# v1-1-0b.net
KiCad netlist of a schematic drawn in EAGLE
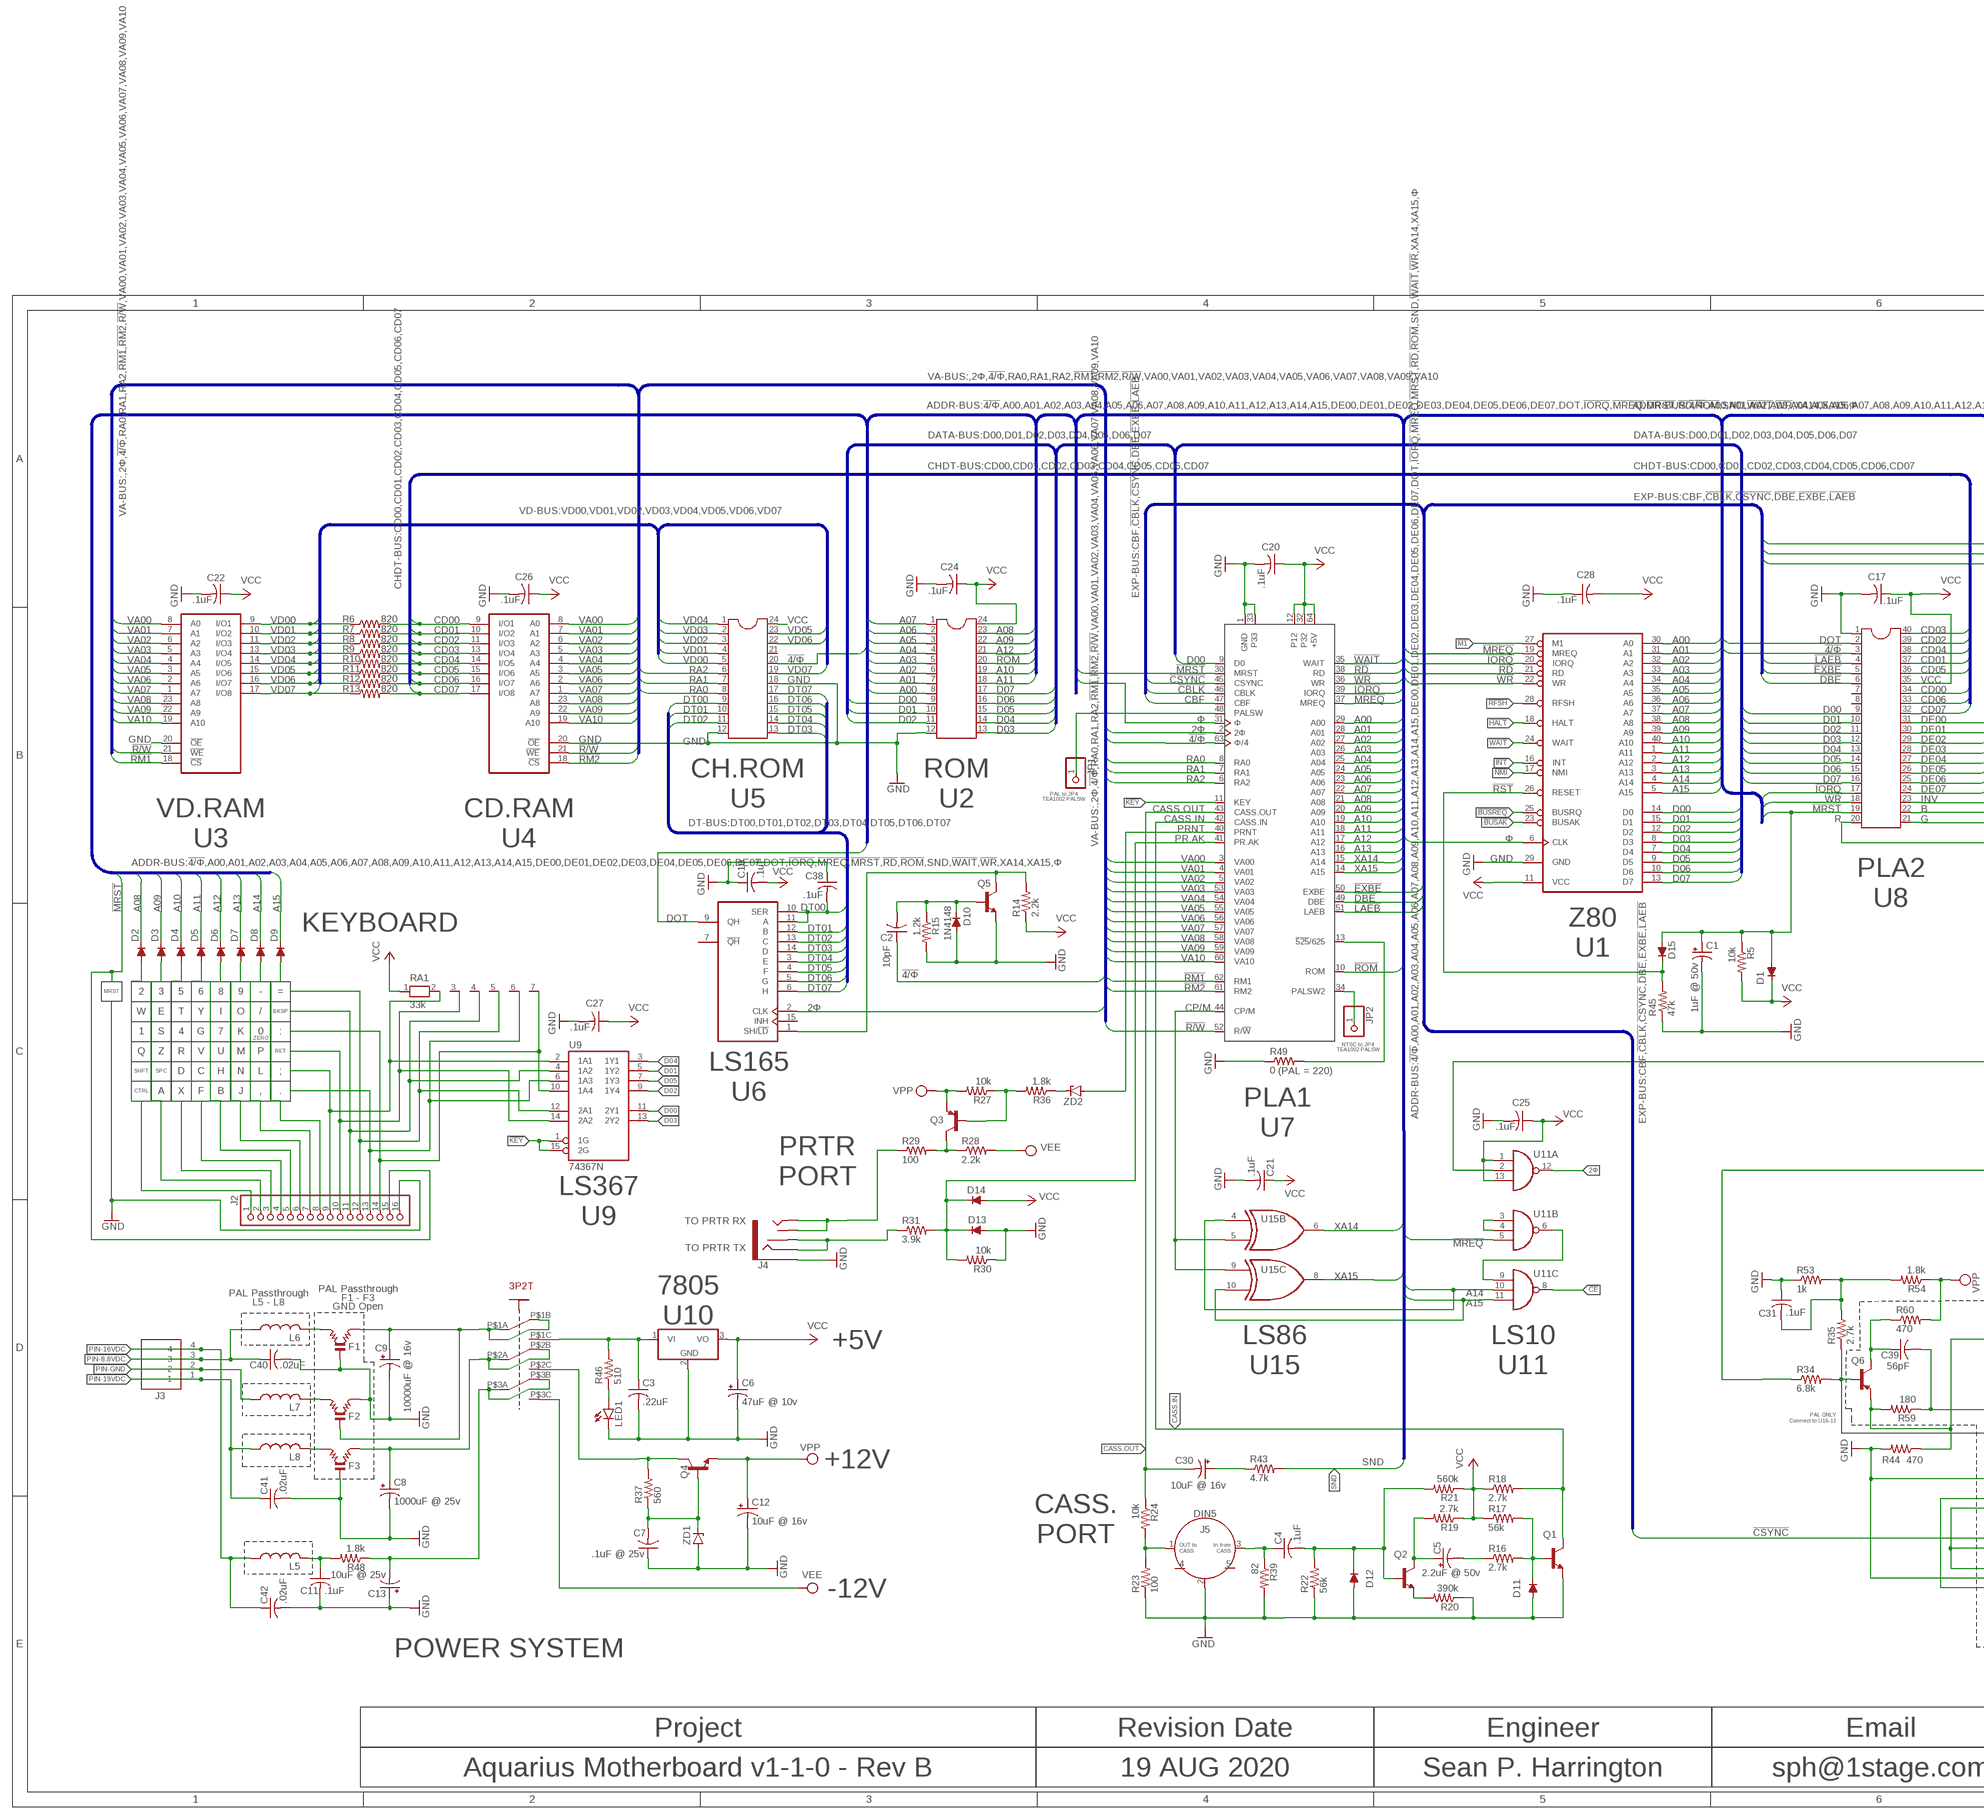
[diagram p0: schematic, sheet 1, part 1 of 2]
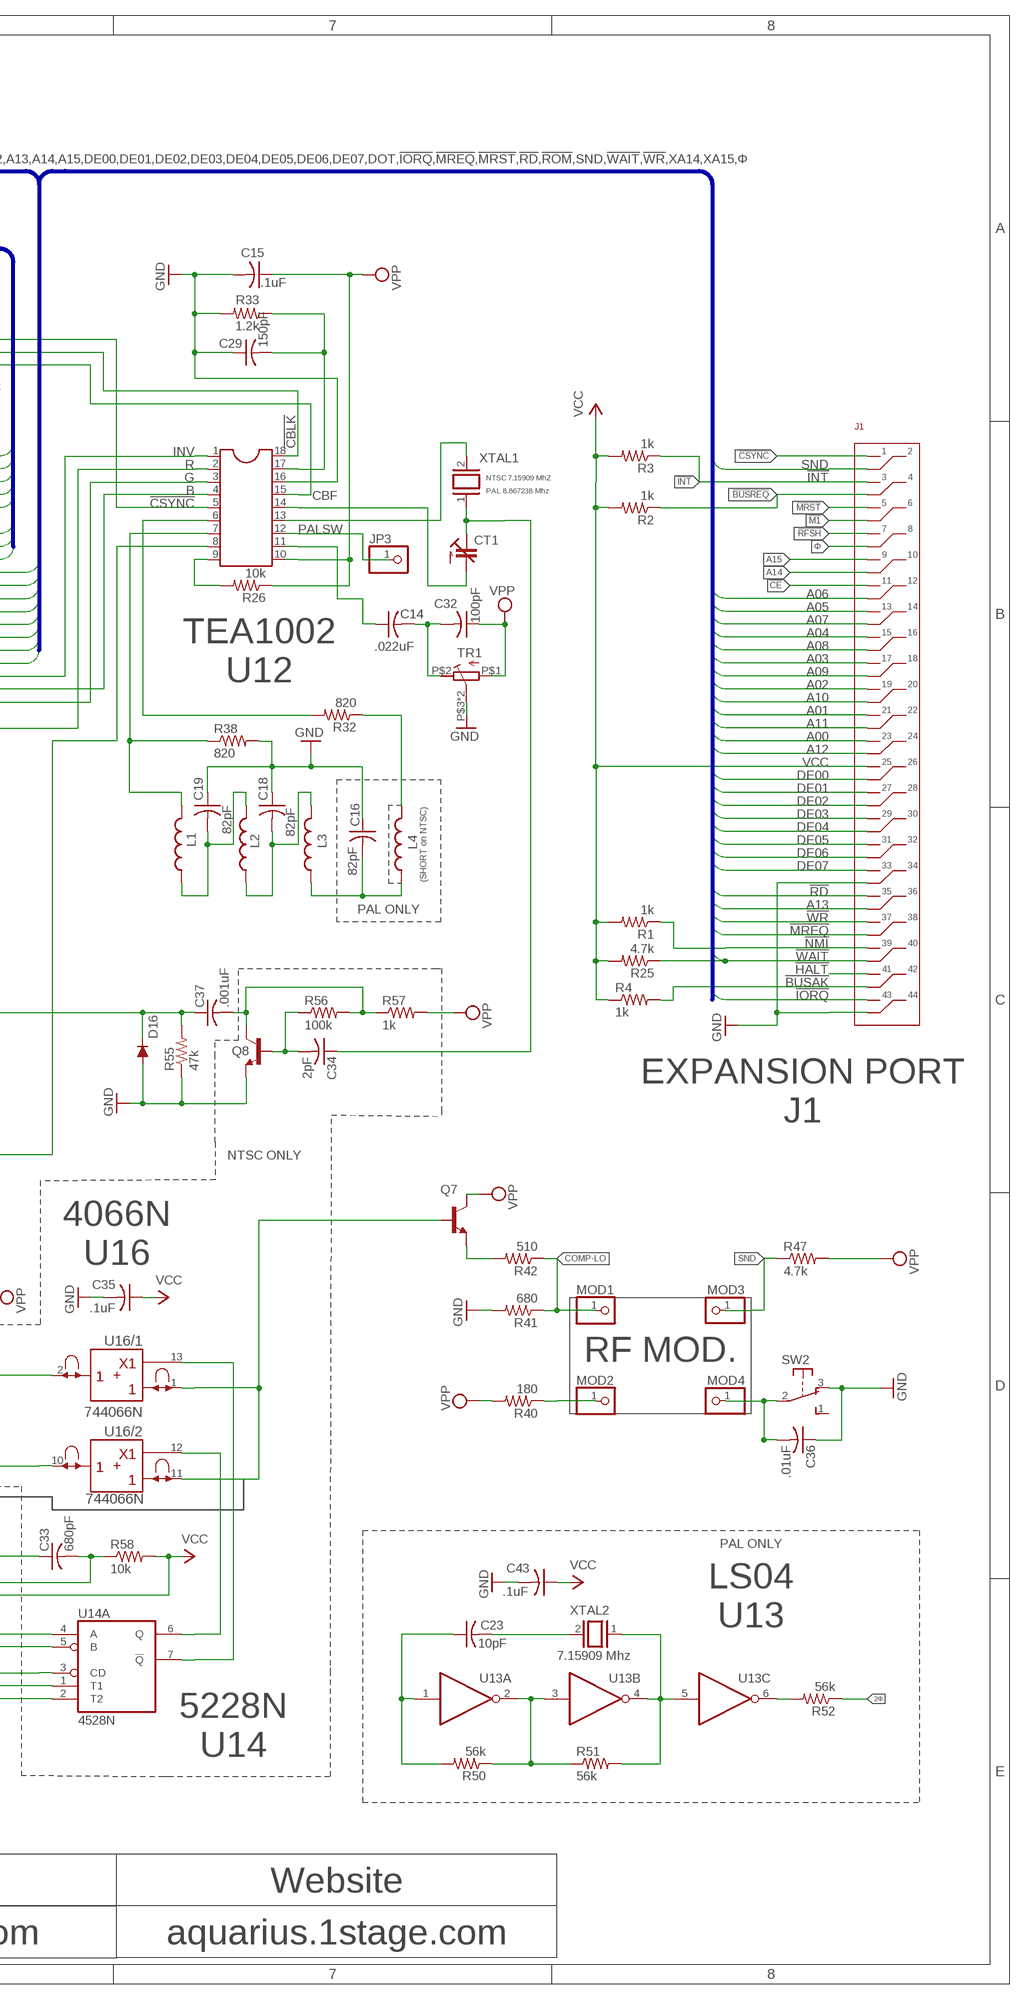
[diagram p1: schematic, sheet 1, part 2 of 2]

(export (version "E")
  (design (tool "Eeschema 10.0.6"))
  (components
    (comp (ref "C1")
      (value "1uF @ 50v")
      (footprint "eagle-import:E2,5-6")
      (libsource (lib "eagle-import") (part "CPOL-USE2.5-6"))
    )
    (comp (ref "C2")
      (value "10pF")
      (footprint "eagle-import:C050-024X044")
      (libsource (lib "eagle-import") (part "C-US050-024X044"))
    )
    (comp (ref "C3")
      (value ".22uF")
      (footprint "eagle-import:C050-025X090")
      (libsource (lib "eagle-import") (part "C-US050-025X090"))
    )
    (comp (ref "C4")
      (value ".1uF")
      (footprint "eagle-import:C050-025X090")
      (libsource (lib "eagle-import") (part "C-US050-025X090"))
    )
    (comp (ref "C5")
      (value "2.2uF @ 50v")
      (footprint "eagle-import:E2,5-6")
      (libsource (lib "eagle-import") (part "CPOL-USE2.5-6"))
    )
    (comp (ref "C6")
      (value "47uF @ 10v")
      (footprint "eagle-import:E2,5-6")
      (libsource (lib "eagle-import") (part "CPOL-USE2.5-6"))
    )
    (comp (ref "C7")
      (value ".1uF @ 25v")
      (footprint "eagle-import:C050-025X090")
      (libsource (lib "eagle-import") (part "C-US050-025X090"))
    )
    (comp (ref "C8")
      (value "1000uF @ 25v")
      (footprint "eagle-import:E7,5-16")
      (libsource (lib "eagle-import") (part "CPOL-USE7.5-16"))
    )
    (comp (ref "C9")
      (value "10000uF @ 16v")
      (footprint "eagle-import:E45-18")
      (libsource (lib "eagle-import") (part "CPOL-USE45-18AXIAL"))
    )
    (comp (ref "C10")
      (value ".1uF")
      (footprint "eagle-import:C050-025X090")
      (libsource (lib "eagle-import") (part "C-US050-025X090"))
    )
    (comp (ref "C11")
      (value ".1uF")
      (footprint "eagle-import:C050-025X090")
      (libsource (lib "eagle-import") (part "C-US050-025X090"))
    )
    (comp (ref "C12")
      (value "10uF @ 16v")
      (footprint "eagle-import:E2,5-6")
      (libsource (lib "eagle-import") (part "CPOL-USE2.5-6"))
    )
    (comp (ref "C13")
      (value "10uF @ 25v")
      (footprint "eagle-import:E2,5-6")
      (libsource (lib "eagle-import") (part "CPOL-USE2.5-6"))
    )
    (comp (ref "C14")
      (value ".022uF")
      (footprint "eagle-import:C050-024X044")
      (libsource (lib "eagle-import") (part "C-US050-024X044"))
    )
    (comp (ref "C15")
      (value ".1uF")
      (footprint "eagle-import:C050-025X090")
      (libsource (lib "eagle-import") (part "C-US050-025X090"))
    )
    (comp (ref "C16")
      (value "82pF")
      (footprint "eagle-import:C050-024X044")
      (libsource (lib "eagle-import") (part "C-US050-024X044"))
    )
    (comp (ref "C17")
      (value ".1uF")
      (footprint "eagle-import:C050-025X090")
      (libsource (lib "eagle-import") (part "C-US050-025X090"))
    )
    (comp (ref "C18")
      (value "82pF")
      (footprint "eagle-import:C050-024X044")
      (libsource (lib "eagle-import") (part "C-US050-024X044"))
    )
    (comp (ref "C19")
      (value "82pF")
      (footprint "eagle-import:C050-024X044")
      (libsource (lib "eagle-import") (part "C-US050-024X044"))
    )
    (comp (ref "C20")
      (value ".1uF")
      (footprint "eagle-import:C050-025X090")
      (libsource (lib "eagle-import") (part "C-US050-025X090"))
    )
    (comp (ref "C21")
      (value ".1uF")
      (footprint "eagle-import:C050-025X090")
      (libsource (lib "eagle-import") (part "C-US050-025X090"))
    )
    (comp (ref "C22")
      (value ".1uF")
      (footprint "eagle-import:C050-025X085")
      (libsource (lib "eagle-import") (part "C-US050-025X085"))
    )
    (comp (ref "C23")
      (value "10pF")
      (footprint "eagle-import:C050-024X044")
      (libsource (lib "eagle-import") (part "C-US050-024X044"))
    )
    (comp (ref "C24")
      (value ".1uF")
      (footprint "eagle-import:C050-025X090")
      (libsource (lib "eagle-import") (part "C-US050-025X090"))
    )
    (comp (ref "C25")
      (value ".1uF")
      (footprint "eagle-import:C050-025X090")
      (libsource (lib "eagle-import") (part "C-US050-025X090"))
    )
    (comp (ref "C26")
      (value ".1uF")
      (footprint "eagle-import:C050-025X085")
      (libsource (lib "eagle-import") (part "C-US050-025X085"))
    )
    (comp (ref "C27")
      (value ".1uF")
      (footprint "eagle-import:C050-025X090")
      (libsource (lib "eagle-import") (part "C-US050-025X090"))
    )
    (comp (ref "C28")
      (value ".1uF")
      (footprint "eagle-import:C050-025X090")
      (libsource (lib "eagle-import") (part "C-US050-025X090"))
    )
    (comp (ref "C29")
      (value "150pF")
      (footprint "eagle-import:C050-024X044")
      (libsource (lib "eagle-import") (part "C-US050-024X044"))
    )
    (comp (ref "C30")
      (value "10uF @ 16v")
      (footprint "eagle-import:E2,5-6")
      (libsource (lib "eagle-import") (part "CPOL-USE2.5-6"))
    )
    (comp (ref "C31")
      (value ".1uF")
      (footprint "eagle-import:C050-024X044")
      (libsource (lib "eagle-import") (part "C-US050-024X044"))
    )
    (comp (ref "C32")
      (value "100pF")
      (footprint "eagle-import:C025-024X044")
      (libsource (lib "eagle-import") (part "C-US025-024X044"))
    )
    (comp (ref "C33")
      (value "680pF")
      (footprint "eagle-import:C050-024X044")
      (libsource (lib "eagle-import") (part "C-US050-024X044"))
    )
    (comp (ref "C34")
      (value "2pF")
      (footprint "eagle-import:C025-024X044")
      (libsource (lib "eagle-import") (part "C-US025-024X044"))
    )
    (comp (ref "C35")
      (value ".1uF")
      (footprint "eagle-import:C050-025X090")
      (libsource (lib "eagle-import") (part "C-US050-025X090"))
    )
    (comp (ref "C36")
      (value ".01uF")
      (footprint "eagle-import:C050-024X044")
      (libsource (lib "eagle-import") (part "C-US050-024X044"))
    )
    (comp (ref "C37")
      (value ".001uF")
      (footprint "eagle-import:C025-030X050")
      (libsource (lib "eagle-import") (part "C-US025-030X050"))
    )
    (comp (ref "C38")
      (value ".1uF")
      (footprint "eagle-import:C050-025X085")
      (libsource (lib "eagle-import") (part "C-US050-025X085"))
    )
    (comp (ref "C39")
      (value "56pF")
      (footprint "eagle-import:C050-024X044")
      (libsource (lib "eagle-import") (part "C-US050-024X044"))
    )
    (comp (ref "C40")
      (value ".02uF")
      (footprint "eagle-import:C050-025X090")
      (libsource (lib "eagle-import") (part "C-US050-025X090"))
    )
    (comp (ref "C41")
      (value ".02uF")
      (footprint "eagle-import:C050-025X090")
      (libsource (lib "eagle-import") (part "C-US050-025X090"))
    )
    (comp (ref "C42")
      (value ".02uF")
      (footprint "eagle-import:C050-025X090")
      (libsource (lib "eagle-import") (part "C-US050-025X090"))
    )
    (comp (ref "C43")
      (value ".1uF")
      (footprint "eagle-import:C050-025X090")
      (libsource (lib "eagle-import") (part "C-US050-025X090"))
    )
    (comp (ref "CT1")
      (value "C-TRIMM808")
      (footprint "eagle-import:CTRIM808-BC")
      (libsource (lib "eagle-import") (part "C-TRIMM808"))
    )
    (comp (ref "D1")
      (value "1N4148")
      (footprint "eagle-import:DO35-10")
      (libsource (lib "eagle-import") (part "1N4148"))
    )
    (comp (ref "D2")
      (value "1N4148H")
      (footprint "eagle-import:DO35-12")
      (libsource (lib "eagle-import") (part "1N4148-12"))
    )
    (comp (ref "D3")
      (value "1N4148H")
      (footprint "eagle-import:DO35-12")
      (libsource (lib "eagle-import") (part "1N4148-12"))
    )
    (comp (ref "D4")
      (value "1N4148H")
      (footprint "eagle-import:DO35-12")
      (libsource (lib "eagle-import") (part "1N4148-12"))
    )
    (comp (ref "D5")
      (value "1N4148H")
      (footprint "eagle-import:DO35-12")
      (libsource (lib "eagle-import") (part "1N4148-12"))
    )
    (comp (ref "D6")
      (value "1N4148H")
      (footprint "eagle-import:DO35-12")
      (libsource (lib "eagle-import") (part "1N4148-12"))
    )
    (comp (ref "D7")
      (value "1N4148H")
      (footprint "eagle-import:DO35-12")
      (libsource (lib "eagle-import") (part "1N4148-12"))
    )
    (comp (ref "D8")
      (value "1N4148H")
      (footprint "eagle-import:DO35-12")
      (libsource (lib "eagle-import") (part "1N4148-12"))
    )
    (comp (ref "D9")
      (value "1N4148H")
      (footprint "eagle-import:DO35-12")
      (libsource (lib "eagle-import") (part "1N4148-12"))
    )
    (comp (ref "D10")
      (value "1N4148")
      (footprint "eagle-import:DO35-10")
      (libsource (lib "eagle-import") (part "1N4148"))
    )
    (comp (ref "D11")
      (value "1N4148")
      (footprint "eagle-import:DO35-10")
      (libsource (lib "eagle-import") (part "1N4148"))
    )
    (comp (ref "D12")
      (value "1N4148")
      (footprint "eagle-import:DO35-10")
      (libsource (lib "eagle-import") (part "1N4148"))
    )
    (comp (ref "D13")
      (value "1N4148")
      (footprint "eagle-import:DO35-10")
      (libsource (lib "eagle-import") (part "1N4148"))
    )
    (comp (ref "D14")
      (value "1N4148")
      (footprint "eagle-import:DO35-10")
      (libsource (lib "eagle-import") (part "1N4148"))
    )
    (comp (ref "D15")
      (value "1N4148")
      (footprint "eagle-import:DO35-10")
      (libsource (lib "eagle-import") (part "1N4148"))
    )
    (comp (ref "D16")
      (value "1N4148")
      (footprint "eagle-import:DO35-10")
      (libsource (lib "eagle-import") (part "1N4148"))
    )
    (comp (ref "F1")
      (value "LCL")
      (footprint "eagle-import:LCL")
      (libsource (lib "eagle-import") (part "LCL"))
    )
    (comp (ref "F2")
      (value "LCL")
      (footprint "eagle-import:LCL")
      (libsource (lib "eagle-import") (part "LCL"))
    )
    (comp (ref "F3")
      (value "LCL")
      (footprint "eagle-import:LCL")
      (libsource (lib "eagle-import") (part "LCL"))
    )
    (comp (ref "J1")
      (value "CR22A-44D-2.54DSA(70)")
      (footprint "eagle-import:CR22A-44D-2.54DSA(70)")
      (libsource (lib "eagle-import") (part "CR22A-44D-2.54DSA(70)"))
    )
    (comp (ref "J2")
      (value "PINHD-1X16")
      (footprint "eagle-import:1X16")
      (libsource (lib "eagle-import") (part "PINHD-1X16"))
    )
    (comp (ref "J3")
      (value "26-60-4040")
      (footprint "eagle-import:SHDR4W155P0X396_1X4_1570X1001X")
      (fields (field (name "MOUSER_PART_NUMBER") "538-26-60-4040"))
      (libsource (lib "eagle-import") (part "26-60-4040"))
    )
    (comp (ref "J4")
      (value "AUDIO_JACK_3.5MM_PTH")
      (footprint "eagle-import:AUDIO-JACK")
      (libsource (lib "eagle-import") (part "AUDIO_JACK_3.5MM_PTH"))
    )
    (comp (ref "J5")
      (value "DIN5")
      (footprint "eagle-import:DIN5-RA-PTH")
      (libsource (lib "eagle-import") (part "DIN5"))
    )
    (comp (ref "JP1")
      (value "PINHD-1X1")
      (footprint "eagle-import:1X01")
      (libsource (lib "eagle-import") (part "PINHD-1X1"))
    )
    (comp (ref "JP2")
      (value "PINHD-1X1")
      (footprint "eagle-import:1X01")
      (libsource (lib "eagle-import") (part "PINHD-1X1"))
    )
    (comp (ref "JP3")
      (value "PINHD-1X1")
      (footprint "eagle-import:1X01")
      (libsource (lib "eagle-import") (part "PINHD-1X1"))
    )
    (comp (ref "L1")
      (value "L-USTFI0305")
      (footprint "eagle-import:TFI0305")
      (libsource (lib "eagle-import") (part "L-USTFI0305"))
    )
    (comp (ref "L2")
      (value "L-USTFI0305")
      (footprint "eagle-import:TFI0305")
      (libsource (lib "eagle-import") (part "L-USTFI0305"))
    )
    (comp (ref "L3")
      (value "L-USTFI0305")
      (footprint "eagle-import:TFI0305")
      (libsource (lib "eagle-import") (part "L-USTFI0305"))
    )
    (comp (ref "L4")
      (value "L-USTFI0305")
      (footprint "eagle-import:TFI0305")
      (libsource (lib "eagle-import") (part "L-USTFI0305"))
    )
    (comp (ref "L5")
      (value "L-USTFI0305")
      (footprint "eagle-import:TFI0305")
      (libsource (lib "eagle-import") (part "L-USTFI0305"))
    )
    (comp (ref "L6")
      (value "L-USTFI0305")
      (footprint "eagle-import:TFI0305")
      (libsource (lib "eagle-import") (part "L-USTFI0305"))
    )
    (comp (ref "L7")
      (value "L-USTFI0305")
      (footprint "eagle-import:TFI0305")
      (libsource (lib "eagle-import") (part "L-USTFI0305"))
    )
    (comp (ref "L8")
      (value "L-USTFI0305")
      (footprint "eagle-import:TFI0305")
      (libsource (lib "eagle-import") (part "L-USTFI0305"))
    )
    (comp (ref "LED1")
      (value "LED5MM")
      (footprint "eagle-import:LED5MM")
      (libsource (lib "eagle-import") (part "LED5MM"))
    )
    (comp (ref "MOD1")
      (value "PINHD-1X1")
      (footprint "eagle-import:1X01")
      (libsource (lib "eagle-import") (part "PINHD-1X1"))
    )
    (comp (ref "MOD2")
      (value "PINHD-1X1")
      (footprint "eagle-import:1X01")
      (libsource (lib "eagle-import") (part "PINHD-1X1"))
    )
    (comp (ref "MOD3")
      (value "PINHD-1X1")
      (footprint "eagle-import:1X01")
      (libsource (lib "eagle-import") (part "PINHD-1X1"))
    )
    (comp (ref "MOD4")
      (value "PINHD-1X1")
      (footprint "eagle-import:1X01")
      (libsource (lib "eagle-import") (part "PINHD-1X1"))
    )
    (comp (ref "Q1")
      (value "-NPN-TO92-E1")
      (footprint "eagle-import:TO92-E1")
      (libsource (lib "eagle-import") (part "-NPN-TO92-E1"))
    )
    (comp (ref "Q2")
      (value "-NPN-TO92-E1")
      (footprint "eagle-import:TO92-E1")
      (libsource (lib "eagle-import") (part "-NPN-TO92-E1"))
    )
    (comp (ref "Q3")
      (value "-PNP-TO92-E1")
      (footprint "eagle-import:TO92-E1")
      (libsource (lib "eagle-import") (part "-PNP-TO92-E1"))
    )
    (comp (ref "Q4")
      (value "-NPN-TO220V")
      (footprint "eagle-import:TO220V")
      (libsource (lib "eagle-import") (part "transistor_402_-NPN-TO220V"))
    )
    (comp (ref "Q5")
      (value "-NPN-TO92-E1")
      (footprint "eagle-import:TO92-E1")
      (libsource (lib "eagle-import") (part "-NPN-TO92-E1"))
    )
    (comp (ref "Q6")
      (value "-PNP-TO92-E1")
      (footprint "eagle-import:TO92-E1")
      (libsource (lib "eagle-import") (part "-PNP-TO92-E1"))
    )
    (comp (ref "Q7")
      (value "-NPN-TO92-E1")
      (footprint "eagle-import:TO92-E1")
      (libsource (lib "eagle-import") (part "-NPN-TO92-E1"))
    )
    (comp (ref "Q8")
      (value "-NPN-TO92-E1")
      (footprint "eagle-import:TO92-E1")
      (libsource (lib "eagle-import") (part "-NPN-TO92-E1"))
    )
    (comp (ref "R1")
      (value "1k")
      (footprint "eagle-import:0207_10")
      (libsource (lib "eagle-import") (part "R-US_0207/10"))
    )
    (comp (ref "R2")
      (value "1k")
      (footprint "eagle-import:0207_10")
      (libsource (lib "eagle-import") (part "R-US_0207/10"))
    )
    (comp (ref "R3")
      (value "1k")
      (footprint "eagle-import:0207_10")
      (libsource (lib "eagle-import") (part "R-US_0207/10"))
    )
    (comp (ref "R4")
      (value "1k")
      (footprint "eagle-import:0207_10")
      (libsource (lib "eagle-import") (part "R-US_0207/10"))
    )
    (comp (ref "R5")
      (value "10k")
      (footprint "eagle-import:0207_10")
      (libsource (lib "eagle-import") (part "R-US_0207/10"))
    )
    (comp (ref "R6")
      (value "820")
      (footprint "eagle-import:0207_10")
      (libsource (lib "eagle-import") (part "R-US_0207/10"))
    )
    (comp (ref "R7")
      (value "820")
      (footprint "eagle-import:0207_10")
      (libsource (lib "eagle-import") (part "R-US_0207/10"))
    )
    (comp (ref "R8")
      (value "820")
      (footprint "eagle-import:0207_10")
      (libsource (lib "eagle-import") (part "R-US_0207/10"))
    )
    (comp (ref "R9")
      (value "820")
      (footprint "eagle-import:0207_10")
      (libsource (lib "eagle-import") (part "R-US_0207/10"))
    )
    (comp (ref "R10")
      (value "820")
      (footprint "eagle-import:0207_10")
      (libsource (lib "eagle-import") (part "R-US_0207/10"))
    )
    (comp (ref "R11")
      (value "820")
      (footprint "eagle-import:0207_10")
      (libsource (lib "eagle-import") (part "R-US_0207/10"))
    )
    (comp (ref "R12")
      (value "820")
      (footprint "eagle-import:0207_10")
      (libsource (lib "eagle-import") (part "R-US_0207/10"))
    )
    (comp (ref "R13")
      (value "820")
      (footprint "eagle-import:0207_10")
      (libsource (lib "eagle-import") (part "R-US_0207/10"))
    )
    (comp (ref "R14")
      (value "2.2k")
      (footprint "eagle-import:0207_10")
      (libsource (lib "eagle-import") (part "R-US_0207/10"))
    )
    (comp (ref "R15")
      (value "1.2k")
      (footprint "eagle-import:0207_10")
      (libsource (lib "eagle-import") (part "R-US_0207/10"))
    )
    (comp (ref "R16")
      (value "2.7k")
      (footprint "eagle-import:0207_10")
      (libsource (lib "eagle-import") (part "R-US_0207/10"))
    )
    (comp (ref "R17")
      (value "56k")
      (footprint "eagle-import:0207_10")
      (libsource (lib "eagle-import") (part "R-US_0207/10"))
    )
    (comp (ref "R18")
      (value "2.7k")
      (footprint "eagle-import:0207_10")
      (libsource (lib "eagle-import") (part "R-US_0207/10"))
    )
    (comp (ref "R19")
      (value "2.7k")
      (footprint "eagle-import:0207_10")
      (libsource (lib "eagle-import") (part "R-US_0207/10"))
    )
    (comp (ref "R20")
      (value "390k")
      (footprint "eagle-import:0207_10")
      (libsource (lib "eagle-import") (part "R-US_0207/10"))
    )
    (comp (ref "R21")
      (value "560k")
      (footprint "eagle-import:0207_10")
      (libsource (lib "eagle-import") (part "R-US_0207/10"))
    )
    (comp (ref "R22")
      (value "56k")
      (footprint "eagle-import:0207_10")
      (libsource (lib "eagle-import") (part "R-US_0207/10"))
    )
    (comp (ref "R23")
      (value "100")
      (footprint "eagle-import:0207_10")
      (libsource (lib "eagle-import") (part "R-US_0207/10"))
    )
    (comp (ref "R24")
      (value "10k")
      (footprint "eagle-import:0207_10")
      (libsource (lib "eagle-import") (part "R-US_0207/10"))
    )
    (comp (ref "R25")
      (value "4.7k")
      (footprint "eagle-import:0207_10")
      (libsource (lib "eagle-import") (part "R-US_0207/10"))
    )
    (comp (ref "R26")
      (value "10k")
      (footprint "eagle-import:0207_10")
      (libsource (lib "eagle-import") (part "R-US_0207/10"))
    )
    (comp (ref "R27")
      (value "10k")
      (footprint "eagle-import:0207_10")
      (libsource (lib "eagle-import") (part "R-US_0207/10"))
    )
    (comp (ref "R28")
      (value "2.2k")
      (footprint "eagle-import:0207_10")
      (libsource (lib "eagle-import") (part "R-US_0207/10"))
    )
    (comp (ref "R29")
      (value "100")
      (footprint "eagle-import:0207_10")
      (libsource (lib "eagle-import") (part "R-US_0207/10"))
    )
    (comp (ref "R30")
      (value "10k")
      (footprint "eagle-import:0207_10")
      (libsource (lib "eagle-import") (part "R-US_0207/10"))
    )
    (comp (ref "R31")
      (value "3.9k")
      (footprint "eagle-import:0207_10")
      (libsource (lib "eagle-import") (part "R-US_0207/10"))
    )
    (comp (ref "R32")
      (value "820")
      (footprint "eagle-import:0207_10")
      (libsource (lib "eagle-import") (part "R-US_0207/10"))
    )
    (comp (ref "R33")
      (value "1.2k")
      (footprint "eagle-import:0207_10")
      (libsource (lib "eagle-import") (part "R-US_0207/10"))
    )
    (comp (ref "R34")
      (value "6.8k")
      (footprint "eagle-import:0207_10")
      (libsource (lib "eagle-import") (part "R-US_0207/10"))
    )
    (comp (ref "R35")
      (value "2.7k")
      (footprint "eagle-import:0207_10")
      (libsource (lib "eagle-import") (part "R-US_0207/10"))
    )
    (comp (ref "R36")
      (value "1.8k")
      (footprint "eagle-import:0207_10")
      (libsource (lib "eagle-import") (part "R-US_0207/10"))
    )
    (comp (ref "R37")
      (value "560")
      (footprint "eagle-import:0207_10")
      (libsource (lib "eagle-import") (part "R-US_0207/10"))
    )
    (comp (ref "R38")
      (value "820")
      (footprint "eagle-import:0207_10")
      (libsource (lib "eagle-import") (part "R-US_0207/10"))
    )
    (comp (ref "R39")
      (value "82")
      (footprint "eagle-import:0207_10")
      (libsource (lib "eagle-import") (part "R-US_0207/10"))
    )
    (comp (ref "R40")
      (value "180")
      (footprint "eagle-import:0207_10")
      (libsource (lib "eagle-import") (part "R-US_0207/10"))
    )
    (comp (ref "R41")
      (value "680")
      (footprint "eagle-import:0207_10")
      (libsource (lib "eagle-import") (part "R-US_0207/10"))
    )
    (comp (ref "R42")
      (value "510")
      (footprint "eagle-import:0207_10")
      (libsource (lib "eagle-import") (part "R-US_0207/10"))
    )
    (comp (ref "R43")
      (value "4.7k")
      (footprint "eagle-import:0207_10")
      (libsource (lib "eagle-import") (part "R-US_0207/10"))
    )
    (comp (ref "R44")
      (value "470")
      (footprint "eagle-import:0207_10")
      (libsource (lib "eagle-import") (part "R-US_0207/10"))
    )
    (comp (ref "R45")
      (value "47k")
      (footprint "eagle-import:0207_10")
      (libsource (lib "eagle-import") (part "R-US_0207/10"))
    )
    (comp (ref "R46")
      (value "510")
      (footprint "eagle-import:0207_10")
      (libsource (lib "eagle-import") (part "R-US_0207/10"))
    )
    (comp (ref "R47")
      (value "4.7k")
      (footprint "eagle-import:0207_10")
      (libsource (lib "eagle-import") (part "R-US_0207/10"))
    )
    (comp (ref "R48")
      (value "1.8k")
      (footprint "eagle-import:0207_10")
      (libsource (lib "eagle-import") (part "R-US_0207/10"))
    )
    (comp (ref "R49")
      (value "0")
      (footprint "eagle-import:0207_7")
      (libsource (lib "eagle-import") (part "R-US_0207/7"))
    )
    (comp (ref "R50")
      (value "56k")
      (footprint "eagle-import:0207_10")
      (libsource (lib "eagle-import") (part "R-US_0207/10"))
    )
    (comp (ref "R51")
      (value "56k")
      (footprint "eagle-import:0207_10")
      (libsource (lib "eagle-import") (part "R-US_0207/10"))
    )
    (comp (ref "R52")
      (value "56k")
      (footprint "eagle-import:0207_10")
      (libsource (lib "eagle-import") (part "R-US_0207/10"))
    )
    (comp (ref "R53")
      (value "1k")
      (footprint "eagle-import:0207_10")
      (libsource (lib "eagle-import") (part "R-US_0207/10"))
    )
    (comp (ref "R54")
      (value "1.8k")
      (footprint "eagle-import:0207_10")
      (libsource (lib "eagle-import") (part "R-US_0207/10"))
    )
    (comp (ref "R55")
      (value "47k")
      (footprint "eagle-import:0207_10")
      (libsource (lib "eagle-import") (part "R-US_0207/10"))
    )
    (comp (ref "R56")
      (value "100k")
      (footprint "eagle-import:0207_10")
      (libsource (lib "eagle-import") (part "R-US_0207/10"))
    )
    (comp (ref "R57")
      (value "1k")
      (footprint "eagle-import:0207_10")
      (libsource (lib "eagle-import") (part "R-US_0207/10"))
    )
    (comp (ref "R58")
      (value "10k")
      (footprint "eagle-import:0207_10")
      (libsource (lib "eagle-import") (part "R-US_0207/10"))
    )
    (comp (ref "R59")
      (value "180")
      (footprint "eagle-import:0207_10")
      (libsource (lib "eagle-import") (part "R-US_0207/10"))
    )
    (comp (ref "R60")
      (value "470")
      (footprint "eagle-import:0207_10")
      (libsource (lib "eagle-import") (part "R-US_0207/10"))
    )
    (comp (ref "RA1")
      (value "33k")
      (footprint "eagle-import:RN-7")
      (libsource (lib "eagle-import") (part "RN06"))
    )
    (comp (ref "SW1")
      (value "3PDT-AQ-SWITCH")
      (footprint "eagle-import:3PDT-AQ-SWITCH")
      (libsource (lib "eagle-import") (part "3PDT-AQ-SWITCH"))
    )
    (comp (ref "SW2")
      (value "9077-1")
      (footprint "eagle-import:9077-1")
      (libsource (lib "eagle-import") (part "9077-1"))
    )
    (comp (ref "TR1")
      (value "R-TRIMM10MM-DUAL")
      (footprint "eagle-import:10MM-DUAL")
      (libsource (lib "eagle-import") (part "R-TRIMM10MM-DUAL"))
    )
    (comp (ref "U1")
      (value "Z80CPU")
      (footprint "eagle-import:DIL40")
      (libsource (lib "eagle-import") (part "Z80CPU"))
    )
    (comp (ref "U2")
      (value "DIL24-6")
      (footprint "eagle-import:DIL24-6")
      (libsource (lib "eagle-import") (part "DIL24-6"))
    )
    (comp (ref "U3")
      (value "6116P")
      (footprint "eagle-import:DIL24-6")
      (libsource (lib "eagle-import") (part "6116P"))
    )
    (comp (ref "U4")
      (value "6116P")
      (footprint "eagle-import:DIL24-6")
      (libsource (lib "eagle-import") (part "6116P"))
    )
    (comp (ref "U5")
      (value "DIL24-6")
      (footprint "eagle-import:DIL24-6")
      (libsource (lib "eagle-import") (part "DIL24-6"))
    )
    (comp (ref "U6")
      (value "74LS165N")
      (footprint "eagle-import:DIL16")
      (libsource (lib "eagle-import") (part "74165NLS"))
    )
    (comp (ref "U7")
      (value "HD61K202P-PLA1")
      (footprint "eagle-import:HD61K202P-PLA1")
      (libsource (lib "eagle-import") (part "HD61K202P-PLA1"))
    )
    (comp (ref "U8")
      (value "DIL40")
      (footprint "eagle-import:DIL40")
      (libsource (lib "eagle-import") (part "DIL40"))
    )
    (comp (ref "U9")
      (value "74367N")
      (footprint "eagle-import:DIL16")
      (libsource (lib "eagle-import") (part "74367N"))
    )
    (comp (ref "U10")
      (value "7805")
      (footprint "eagle-import:TO220V")
      (libsource (lib "eagle-import") (part "78TV05"))
    )
    (comp (ref "U11")
      (value "74LS10N")
      (footprint "eagle-import:DIL14")
      (libsource (lib "eagle-import") (part "7410NLS"))
    )
    (comp (ref "U12")
      (value "DIL18")
      (footprint "eagle-import:DIL18")
      (libsource (lib "eagle-import") (part "DIL18"))
    )
    (comp (ref "U13")
      (value "74LS04N")
      (footprint "eagle-import:DIL14")
      (libsource (lib "eagle-import") (part "7404NLS"))
    )
    (comp (ref "U14")
      (value "4528N")
      (footprint "eagle-import:DIL16")
      (libsource (lib "eagle-import") (part "4528N"))
    )
    (comp (ref "U15")
      (value "74LS86N")
      (footprint "eagle-import:DIL14")
      (libsource (lib "eagle-import") (part "7486NLS"))
    )
    (comp (ref "U16")
      (value "744066N")
      (footprint "eagle-import:DIL14")
      (libsource (lib "eagle-import") (part "744066N"))
    )
    (comp (ref "XTAL1")
      (value "7.15909 MhZ")
      (footprint "eagle-import:Q")
      (libsource (lib "eagle-import") (part "XTAL"))
    )
    (comp (ref "XTAL2")
      (value "7.15909 Mhz")
      (footprint "eagle-import:Q")
      (libsource (lib "eagle-import") (part "XTAL"))
    )
    (comp (ref "ZD1")
      (value "ZENER-DIODEZD-10")
      (footprint "eagle-import:ZDIO-10")
      (libsource (lib "eagle-import") (part "ZENER-DIODEZD-10"))
    )
    (comp (ref "ZD2")
      (value "ZENER-DIODEZD-7.5")
      (footprint "eagle-import:ZDIO-7.5")
      (libsource (lib "eagle-import") (part "ZENER-DIODEZD-7.5"))
    )
  )
  (nets
    (net (code "8") (name "/A00") (class "Default")
      (node (ref "J1") (pin "P$23") (pinfunction "X23_P$23") (pintype "bidirectional"))
      (node (ref "U1") (pin "30") (pinfunction "A0_30") (pintype "output"))
      (node (ref "U2") (pin "8") (pinfunction "8_8") (pintype "passive"))
      (node (ref "U7") (pin "29") (pinfunction "A00_29") (pintype "bidirectional"))
    )
    (net (code "9") (name "/A01") (class "Default")
      (node (ref "J1") (pin "P$21") (pinfunction "X21_P$21") (pintype "bidirectional"))
      (node (ref "U1") (pin "31") (pinfunction "A1_31") (pintype "output"))
      (node (ref "U2") (pin "7") (pinfunction "7_7") (pintype "passive"))
      (node (ref "U7") (pin "28") (pinfunction "A01_28") (pintype "bidirectional"))
    )
    (net (code "10") (name "/A02") (class "Default")
      (node (ref "J1") (pin "P$19") (pinfunction "X19_P$19") (pintype "bidirectional"))
      (node (ref "U1") (pin "32") (pinfunction "A2_32") (pintype "output"))
      (node (ref "U2") (pin "6") (pinfunction "6_6") (pintype "passive"))
      (node (ref "U7") (pin "27") (pinfunction "A02_27") (pintype "bidirectional"))
    )
    (net (code "11") (name "/A03") (class "Default")
      (node (ref "J1") (pin "P$17") (pinfunction "X17_P$17") (pintype "bidirectional"))
      (node (ref "U1") (pin "33") (pinfunction "A3_33") (pintype "output"))
      (node (ref "U2") (pin "5") (pinfunction "5_5") (pintype "passive"))
      (node (ref "U7") (pin "26") (pinfunction "A03_26") (pintype "bidirectional"))
    )
    (net (code "12") (name "/A04") (class "Default")
      (node (ref "J1") (pin "P$15") (pinfunction "X15_P$15") (pintype "bidirectional"))
      (node (ref "U1") (pin "34") (pinfunction "A4_34") (pintype "output"))
      (node (ref "U2") (pin "4") (pinfunction "4_4") (pintype "passive"))
      (node (ref "U7") (pin "25") (pinfunction "A04_25") (pintype "bidirectional"))
    )
    (net (code "13") (name "/A05") (class "Default")
      (node (ref "J1") (pin "P$13") (pinfunction "X13_P$13") (pintype "bidirectional"))
      (node (ref "U1") (pin "35") (pinfunction "A5_35") (pintype "output"))
      (node (ref "U2") (pin "3") (pinfunction "3_3") (pintype "passive"))
      (node (ref "U7") (pin "24") (pinfunction "A05_24") (pintype "bidirectional"))
    )
    (net (code "14") (name "/A06") (class "Default")
      (node (ref "J1") (pin "P$12") (pinfunction "X12_P$12") (pintype "bidirectional"))
      (node (ref "U1") (pin "36") (pinfunction "A6_36") (pintype "output"))
      (node (ref "U2") (pin "2") (pinfunction "2_2") (pintype "passive"))
      (node (ref "U7") (pin "23") (pinfunction "A06_23") (pintype "bidirectional"))
    )
    (net (code "15") (name "/A07") (class "Default")
      (node (ref "J1") (pin "P$14") (pinfunction "X14_P$14") (pintype "bidirectional"))
      (node (ref "U1") (pin "37") (pinfunction "A7_37") (pintype "output"))
      (node (ref "U2") (pin "1") (pinfunction "1_1") (pintype "passive"))
      (node (ref "U7") (pin "22") (pinfunction "A07_22") (pintype "bidirectional"))
    )
    (net (code "16") (name "/A08") (class "Default")
      (node (ref "D2") (pin "C") (pinfunction "C_C") (pintype "passive"))
      (node (ref "J1") (pin "P$16") (pinfunction "X16_P$16") (pintype "bidirectional"))
      (node (ref "U1") (pin "38") (pinfunction "A8_38") (pintype "output"))
      (node (ref "U2") (pin "23") (pinfunction "23_23") (pintype "passive"))
      (node (ref "U7") (pin "21") (pinfunction "A08_21") (pintype "bidirectional"))
    )
    (net (code "17") (name "/A09") (class "Default")
      (node (ref "D3") (pin "C") (pinfunction "C_C") (pintype "passive"))
      (node (ref "J1") (pin "P$18") (pinfunction "X18_P$18") (pintype "bidirectional"))
      (node (ref "U1") (pin "39") (pinfunction "A9_39") (pintype "output"))
      (node (ref "U2") (pin "22") (pinfunction "22_22") (pintype "passive"))
      (node (ref "U7") (pin "20") (pinfunction "A09_20") (pintype "bidirectional"))
    )
    (net (code "18") (name "/A10") (class "Default")
      (node (ref "D4") (pin "C") (pinfunction "C_C") (pintype "passive"))
      (node (ref "J1") (pin "P$20") (pinfunction "X20_P$20") (pintype "bidirectional"))
      (node (ref "U1") (pin "40") (pinfunction "A10_40") (pintype "output"))
      (node (ref "U2") (pin "19") (pinfunction "19_19") (pintype "passive"))
      (node (ref "U7") (pin "19") (pinfunction "A10_19") (pintype "bidirectional"))
    )
    (net (code "19") (name "/A11") (class "Default")
      (node (ref "D5") (pin "C") (pinfunction "C_C") (pintype "passive"))
      (node (ref "J1") (pin "P$22") (pinfunction "X22_P$22") (pintype "bidirectional"))
      (node (ref "U1") (pin "1") (pinfunction "A11_1") (pintype "output"))
      (node (ref "U2") (pin "18") (pinfunction "18_18") (pintype "passive"))
      (node (ref "U7") (pin "18") (pinfunction "A11_18") (pintype "bidirectional"))
    )
    (net (code "20") (name "/A12") (class "Default")
      (node (ref "D6") (pin "C") (pinfunction "C_C") (pintype "passive"))
      (node (ref "J1") (pin "P$24") (pinfunction "X24_P$24") (pintype "bidirectional"))
      (node (ref "U1") (pin "2") (pinfunction "A12_2") (pintype "output"))
      (node (ref "U2") (pin "21") (pinfunction "21_21") (pintype "passive"))
      (node (ref "U7") (pin "17") (pinfunction "A12_17") (pintype "bidirectional"))
    )
    (net (code "21") (name "/A13") (class "Default")
      (node (ref "D7") (pin "C") (pinfunction "C_C") (pintype "passive"))
      (node (ref "J1") (pin "P$36") (pinfunction "X36_P$36") (pintype "bidirectional"))
      (node (ref "U1") (pin "3") (pinfunction "A13_3") (pintype "output"))
      (node (ref "U7") (pin "16") (pinfunction "A13_16") (pintype "bidirectional"))
    )
    (net (code "22") (name "/B") (class "Default")
      (node (ref "U12") (pin "4") (pinfunction "4_4") (pintype "passive"))
      (node (ref "U8") (pin "22") (pinfunction "22_22") (pintype "passive"))
    )
    (net (code "23") (name "/CBF") (class "Default")
      (node (ref "U12") (pin "15") (pinfunction "15_15") (pintype "passive"))
      (node (ref "U7") (pin "47") (pinfunction "CBF_47") (pintype "bidirectional"))
    )
    (net (code "24") (name "/CD00") (class "Default")
      (node (ref "R6") (pin "2") (pinfunction "2_2") (pintype "passive"))
      (node (ref "U4") (pin "9") (pinfunction "I/O1_9") (pintype "bidirectional"))
      (node (ref "U8") (pin "34") (pinfunction "34_34") (pintype "passive"))
    )
    (net (code "25") (name "/CD01") (class "Default")
      (node (ref "R7") (pin "2") (pinfunction "2_2") (pintype "passive"))
      (node (ref "U4") (pin "10") (pinfunction "I/O2_10") (pintype "bidirectional"))
      (node (ref "U8") (pin "37") (pinfunction "37_37") (pintype "passive"))
    )
    (net (code "26") (name "/CD02") (class "Default")
      (node (ref "R8") (pin "2") (pinfunction "2_2") (pintype "passive"))
      (node (ref "U4") (pin "11") (pinfunction "I/O3_11") (pintype "bidirectional"))
      (node (ref "U8") (pin "39") (pinfunction "39_39") (pintype "passive"))
    )
    (net (code "27") (name "/CD03") (class "Default")
      (node (ref "R9") (pin "2") (pinfunction "2_2") (pintype "passive"))
      (node (ref "U4") (pin "13") (pinfunction "I/O4_13") (pintype "bidirectional"))
      (node (ref "U8") (pin "40") (pinfunction "40_40") (pintype "passive"))
    )
    (net (code "28") (name "/CD04") (class "Default")
      (node (ref "R10") (pin "2") (pinfunction "2_2") (pintype "passive"))
      (node (ref "U4") (pin "14") (pinfunction "I/O5_14") (pintype "bidirectional"))
      (node (ref "U8") (pin "38") (pinfunction "38_38") (pintype "passive"))
    )
    (net (code "29") (name "/CD05") (class "Default")
      (node (ref "R11") (pin "2") (pinfunction "2_2") (pintype "passive"))
      (node (ref "U4") (pin "15") (pinfunction "I/O6_15") (pintype "bidirectional"))
      (node (ref "U8") (pin "36") (pinfunction "36_36") (pintype "passive"))
    )
    (net (code "30") (name "/CD06") (class "Default")
      (node (ref "R12") (pin "2") (pinfunction "2_2") (pintype "passive"))
      (node (ref "U4") (pin "16") (pinfunction "I/O7_16") (pintype "bidirectional"))
      (node (ref "U8") (pin "33") (pinfunction "33_33") (pintype "passive"))
    )
    (net (code "31") (name "/CD07") (class "Default")
      (node (ref "R13") (pin "2") (pinfunction "2_2") (pintype "passive"))
      (node (ref "U4") (pin "17") (pinfunction "I/O8_17") (pintype "bidirectional"))
      (node (ref "U8") (pin "32") (pinfunction "32_32") (pintype "passive"))
    )
    (net (code "32") (name "/CP{slash}M") (class "Default")
      (node (ref "U15") (pin "5") (pinfunction "I1_5") (pintype "input"))
      (node (ref "U15") (pin "9") (pinfunction "I0_9") (pintype "input"))
      (node (ref "U7") (pin "44") (pinfunction "CP/M_44") (pintype "bidirectional"))
    )
    (net (code "33") (name "/D06") (class "Default")
      (node (ref "U1") (pin "10") (pinfunction "D6_10") (pintype "bidirectional"))
      (node (ref "U2") (pin "16") (pinfunction "16_16") (pintype "passive"))
      (node (ref "U8") (pin "15") (pinfunction "15_15") (pintype "passive"))
    )
    (net (code "34") (name "/D07") (class "Default")
      (node (ref "U1") (pin "13") (pinfunction "D7_13") (pintype "bidirectional"))
      (node (ref "U2") (pin "17") (pinfunction "17_17") (pintype "passive"))
      (node (ref "U8") (pin "16") (pinfunction "16_16") (pintype "passive"))
    )
    (net (code "35") (name "/DE00") (class "Default")
      (node (ref "J1") (pin "P$26") (pinfunction "X26_P$26") (pintype "bidirectional"))
      (node (ref "U8") (pin "31") (pinfunction "31_31") (pintype "passive"))
    )
    (net (code "36") (name "/DE01") (class "Default")
      (node (ref "J1") (pin "P$27") (pinfunction "X27_P$27") (pintype "bidirectional"))
      (node (ref "U8") (pin "30") (pinfunction "30_30") (pintype "passive"))
    )
    (net (code "37") (name "/DE02") (class "Default")
      (node (ref "J1") (pin "P$28") (pinfunction "X28_P$28") (pintype "bidirectional"))
      (node (ref "U8") (pin "29") (pinfunction "29_29") (pintype "passive"))
    )
    (net (code "38") (name "/DE03") (class "Default")
      (node (ref "J1") (pin "P$29") (pinfunction "X29_P$29") (pintype "bidirectional"))
      (node (ref "U8") (pin "28") (pinfunction "28_28") (pintype "passive"))
    )
    (net (code "39") (name "/DE04") (class "Default")
      (node (ref "J1") (pin "P$30") (pinfunction "X30_P$30") (pintype "bidirectional"))
      (node (ref "U8") (pin "27") (pinfunction "27_27") (pintype "passive"))
    )
    (net (code "40") (name "/DE05") (class "Default")
      (node (ref "J1") (pin "P$31") (pinfunction "X31_P$31") (pintype "bidirectional"))
      (node (ref "U8") (pin "26") (pinfunction "26_26") (pintype "passive"))
    )
    (net (code "41") (name "/DE06") (class "Default")
      (node (ref "J1") (pin "P$32") (pinfunction "X32_P$32") (pintype "bidirectional"))
      (node (ref "U8") (pin "25") (pinfunction "25_25") (pintype "passive"))
    )
    (net (code "42") (name "/DE07") (class "Default")
      (node (ref "J1") (pin "P$33") (pinfunction "X33_P$33") (pintype "bidirectional"))
      (node (ref "U8") (pin "24") (pinfunction "24_24") (pintype "passive"))
    )
    (net (code "43") (name "/DOT") (class "Default")
      (node (ref "U6") (pin "9") (pinfunction "QH_9") (pintype "output"))
      (node (ref "U8") (pin "2") (pinfunction "2_2") (pintype "passive"))
    )
    (net (code "44") (name "/DT00") (class "Default")
      (node (ref "C38") (pin "2") (pinfunction "2_2") (pintype "passive"))
      (node (ref "U5") (pin "9") (pinfunction "9_9") (pintype "passive"))
      (node (ref "U6") (pin "10") (pinfunction "SER_10") (pintype "input"))
      (node (ref "U6") (pin "11") (pinfunction "A_11") (pintype "input"))
    )
    (net (code "45") (name "/DT01") (class "Default")
      (node (ref "U5") (pin "10") (pinfunction "10_10") (pintype "passive"))
      (node (ref "U6") (pin "12") (pinfunction "B_12") (pintype "input"))
    )
    (net (code "46") (name "/DT02") (class "Default")
      (node (ref "U5") (pin "11") (pinfunction "11_11") (pintype "passive"))
      (node (ref "U6") (pin "13") (pinfunction "C_13") (pintype "input"))
    )
    (net (code "47") (name "/DT03") (class "Default")
      (node (ref "U5") (pin "13") (pinfunction "13_13") (pintype "passive"))
      (node (ref "U6") (pin "14") (pinfunction "D_14") (pintype "input"))
    )
    (net (code "48") (name "/DT04") (class "Default")
      (node (ref "U5") (pin "14") (pinfunction "14_14") (pintype "passive"))
      (node (ref "U6") (pin "3") (pinfunction "E_3") (pintype "input"))
    )
    (net (code "49") (name "/DT05") (class "Default")
      (node (ref "U5") (pin "15") (pinfunction "15_15") (pintype "passive"))
      (node (ref "U6") (pin "4") (pinfunction "F_4") (pintype "input"))
    )
    (net (code "50") (name "/DT06") (class "Default")
      (node (ref "U5") (pin "16") (pinfunction "16_16") (pintype "passive"))
      (node (ref "U6") (pin "5") (pinfunction "G_5") (pintype "input"))
    )
    (net (code "51") (name "/DT07") (class "Default")
      (node (ref "U5") (pin "17") (pinfunction "17_17") (pintype "passive"))
      (node (ref "U6") (pin "6") (pinfunction "H_6") (pintype "input"))
    )
    (net (code "52") (name "/G") (class "Default")
      (node (ref "U12") (pin "3") (pinfunction "3_3") (pintype "passive"))
      (node (ref "U8") (pin "21") (pinfunction "21_21") (pintype "passive"))
    )
    (net (code "53") (name "/INV") (class "Default")
      (node (ref "U12") (pin "1") (pinfunction "1_1") (pintype "passive"))
      (node (ref "U8") (pin "23") (pinfunction "23_23") (pintype "passive"))
    )
    (net (code "54") (name "/PALSW") (class "Default")
      (node (ref "JP3") (pin "1") (pinfunction "1_1") (pintype "passive"))
      (node (ref "U12") (pin "12") (pinfunction "12_12") (pintype "passive"))
    )
    (net (code "55") (name "/PR.AK") (class "Default")
      (node (ref "D13") (pin "C") (pinfunction "C_C") (pintype "passive"))
      (node (ref "D14") (pin "C") (pinfunction "C_C") (pintype "passive"))
      (node (ref "R30") (pin "2") (pinfunction "2_2") (pintype "passive"))
      (node (ref "R31") (pin "2") (pinfunction "2_2") (pintype "passive"))
      (node (ref "U7") (pin "41") (pinfunction "PR.AK_41") (pintype "bidirectional"))
    )
    (net (code "56") (name "/PRNT") (class "Default")
      (node (ref "U7") (pin "40") (pinfunction "PRNT_40") (pintype "bidirectional"))
      (node (ref "ZD2") (pin "A") (pinfunction "A_A") (pintype "passive"))
    )
    (net (code "57") (name "/R") (class "Default")
      (node (ref "U12") (pin "2") (pinfunction "2_2") (pintype "passive"))
      (node (ref "U8") (pin "20") (pinfunction "20_20") (pintype "passive"))
    )
    (net (code "58") (name "/RA0") (class "Default")
      (node (ref "U5") (pin "8") (pinfunction "8_8") (pintype "passive"))
      (node (ref "U7") (pin "8") (pinfunction "RA0_8") (pintype "bidirectional"))
    )
    (net (code "59") (name "/RA1") (class "Default")
      (node (ref "U5") (pin "7") (pinfunction "7_7") (pintype "passive"))
      (node (ref "U7") (pin "7") (pinfunction "RA1_7") (pintype "bidirectional"))
    )
    (net (code "60") (name "/RA2") (class "Default")
      (node (ref "U5") (pin "6") (pinfunction "6_6") (pintype "passive"))
      (node (ref "U7") (pin "6") (pinfunction "RA2_6") (pintype "bidirectional"))
    )
    (net (code "61") (name "/VA00") (class "Default")
      (node (ref "U3") (pin "8") (pinfunction "A0_8") (pintype "input"))
      (node (ref "U4") (pin "8") (pinfunction "A0_8") (pintype "input"))
      (node (ref "U7") (pin "3") (pinfunction "VA00_3") (pintype "bidirectional"))
    )
    (net (code "62") (name "/VA01") (class "Default")
      (node (ref "U3") (pin "7") (pinfunction "A1_7") (pintype "input"))
      (node (ref "U4") (pin "7") (pinfunction "A1_7") (pintype "input"))
      (node (ref "U7") (pin "4") (pinfunction "VA01_4") (pintype "bidirectional"))
    )
    (net (code "63") (name "/VA02") (class "Default")
      (node (ref "U3") (pin "6") (pinfunction "A2_6") (pintype "input"))
      (node (ref "U4") (pin "6") (pinfunction "A2_6") (pintype "input"))
      (node (ref "U7") (pin "5") (pinfunction "VA02_5") (pintype "bidirectional"))
    )
    (net (code "64") (name "/VA03") (class "Default")
      (node (ref "U3") (pin "5") (pinfunction "A3_5") (pintype "input"))
      (node (ref "U4") (pin "5") (pinfunction "A3_5") (pintype "input"))
      (node (ref "U7") (pin "53") (pinfunction "VA03_53") (pintype "bidirectional"))
    )
    (net (code "65") (name "/VA04") (class "Default")
      (node (ref "U3") (pin "4") (pinfunction "A4_4") (pintype "input"))
      (node (ref "U4") (pin "4") (pinfunction "A4_4") (pintype "input"))
      (node (ref "U7") (pin "54") (pinfunction "VA04_54") (pintype "bidirectional"))
    )
    (net (code "66") (name "/VA05") (class "Default")
      (node (ref "U3") (pin "3") (pinfunction "A5_3") (pintype "input"))
      (node (ref "U4") (pin "3") (pinfunction "A5_3") (pintype "input"))
      (node (ref "U7") (pin "55") (pinfunction "VA05_55") (pintype "bidirectional"))
    )
    (net (code "67") (name "/VA06") (class "Default")
      (node (ref "U3") (pin "2") (pinfunction "A6_2") (pintype "input"))
      (node (ref "U4") (pin "2") (pinfunction "A6_2") (pintype "input"))
      (node (ref "U7") (pin "56") (pinfunction "VA06_56") (pintype "bidirectional"))
    )
    (net (code "68") (name "/VA07") (class "Default")
      (node (ref "U3") (pin "1") (pinfunction "A7_1") (pintype "input"))
      (node (ref "U4") (pin "1") (pinfunction "A7_1") (pintype "input"))
      (node (ref "U7") (pin "57") (pinfunction "VA07_57") (pintype "bidirectional"))
    )
    (net (code "69") (name "/VA08") (class "Default")
      (node (ref "U3") (pin "23") (pinfunction "A8_23") (pintype "input"))
      (node (ref "U4") (pin "23") (pinfunction "A8_23") (pintype "input"))
      (node (ref "U7") (pin "58") (pinfunction "VA08_58") (pintype "bidirectional"))
    )
    (net (code "70") (name "/VA09") (class "Default")
      (node (ref "U3") (pin "22") (pinfunction "A9_22") (pintype "input"))
      (node (ref "U4") (pin "22") (pinfunction "A9_22") (pintype "input"))
      (node (ref "U7") (pin "59") (pinfunction "VA09_59") (pintype "bidirectional"))
    )
    (net (code "71") (name "/VA10") (class "Default")
      (node (ref "U3") (pin "19") (pinfunction "A10_19") (pintype "input"))
      (node (ref "U4") (pin "19") (pinfunction "A10_19") (pintype "input"))
      (node (ref "U7") (pin "60") (pinfunction "VA10_60") (pintype "bidirectional"))
    )
    (net (code "72") (name "/VD00") (class "Default")
      (node (ref "R6") (pin "1") (pinfunction "1_1") (pintype "passive"))
      (node (ref "U3") (pin "9") (pinfunction "I/O1_9") (pintype "bidirectional"))
      (node (ref "U5") (pin "5") (pinfunction "5_5") (pintype "passive"))
    )
    (net (code "73") (name "/VD01") (class "Default")
      (node (ref "R7") (pin "1") (pinfunction "1_1") (pintype "passive"))
      (node (ref "U3") (pin "10") (pinfunction "I/O2_10") (pintype "bidirectional"))
      (node (ref "U5") (pin "4") (pinfunction "4_4") (pintype "passive"))
    )
    (net (code "74") (name "/VD02") (class "Default")
      (node (ref "R8") (pin "1") (pinfunction "1_1") (pintype "passive"))
      (node (ref "U3") (pin "11") (pinfunction "I/O3_11") (pintype "bidirectional"))
      (node (ref "U5") (pin "3") (pinfunction "3_3") (pintype "passive"))
    )
    (net (code "75") (name "/VD03") (class "Default")
      (node (ref "R9") (pin "1") (pinfunction "1_1") (pintype "passive"))
      (node (ref "U3") (pin "13") (pinfunction "I/O4_13") (pintype "bidirectional"))
      (node (ref "U5") (pin "2") (pinfunction "2_2") (pintype "passive"))
    )
    (net (code "76") (name "/VD04") (class "Default")
      (node (ref "R10") (pin "1") (pinfunction "1_1") (pintype "passive"))
      (node (ref "U3") (pin "14") (pinfunction "I/O5_14") (pintype "bidirectional"))
      (node (ref "U5") (pin "1") (pinfunction "1_1") (pintype "passive"))
    )
    (net (code "77") (name "/VD05") (class "Default")
      (node (ref "R11") (pin "1") (pinfunction "1_1") (pintype "passive"))
      (node (ref "U3") (pin "15") (pinfunction "I/O6_15") (pintype "bidirectional"))
      (node (ref "U5") (pin "23") (pinfunction "23_23") (pintype "passive"))
    )
    (net (code "78") (name "/VD06") (class "Default")
      (node (ref "R12") (pin "1") (pinfunction "1_1") (pintype "passive"))
      (node (ref "U3") (pin "16") (pinfunction "I/O7_16") (pintype "bidirectional"))
      (node (ref "U5") (pin "22") (pinfunction "22_22") (pintype "passive"))
    )
    (net (code "79") (name "/VD07") (class "Default")
      (node (ref "R13") (pin "1") (pinfunction "1_1") (pintype "passive"))
      (node (ref "U3") (pin "17") (pinfunction "I/O8_17") (pintype "bidirectional"))
      (node (ref "U5") (pin "19") (pinfunction "19_19") (pintype "passive"))
    )
    (net (code "80") (name "/XA14") (class "Default")
      (node (ref "U15") (pin "6") (pinfunction "O_6") (pintype "output"))
      (node (ref "U7") (pin "15") (pinfunction "A14_15") (pintype "bidirectional"))
    )
    (net (code "81") (name "/XA15") (class "Default")
      (node (ref "U15") (pin "8") (pinfunction "O_8") (pintype "output"))
      (node (ref "U7") (pin "14") (pinfunction "A15_14") (pintype "bidirectional"))
    )
    (net (code "89") (name "/~{4{slash}Φ}") (class "Default")
      (node (ref "C2") (pin "1") (pinfunction "1_1") (pintype "passive"))
      (node (ref "U5") (pin "20") (pinfunction "20_20") (pintype "passive"))
      (node (ref "U7") (pin "63") (pinfunction "Φ/4_63") (pintype "bidirectional"))
      (node (ref "U8") (pin "3") (pinfunction "3_3") (pintype "passive"))
    )
    (net (code "90") (name "/~{BUSAK}") (class "Default")
      (node (ref "J1") (pin "P$42") (pinfunction "X42_P$42") (pintype "bidirectional"))
      (node (ref "R4") (pin "2") (pinfunction "2_2") (pintype "passive"))
      (node (ref "U1") (pin "23") (pinfunction "BUSAK_23") (pintype "output"))
    )
    (net (code "91") (name "/~{BUSREQ}") (class "Default")
      (node (ref "J1") (pin "P$4") (pinfunction "X4_P$4") (pintype "bidirectional"))
      (node (ref "R2") (pin "1") (pinfunction "1_1") (pintype "passive"))
      (node (ref "U1") (pin "25") (pinfunction "BUSRQ_25") (pintype "input"))
    )
    (net (code "92") (name "/~{CBLK}") (class "Default")
      (node (ref "U12") (pin "18") (pinfunction "18_18") (pintype "passive"))
      (node (ref "U7") (pin "46") (pinfunction "CBLK_46") (pintype "bidirectional"))
    )
    (net (code "93") (name "/~{CE}") (class "Default")
      (node (ref "J1") (pin "P$11") (pinfunction "X11_P$11") (pintype "bidirectional"))
      (node (ref "U11") (pin "8") (pinfunction "O_8") (pintype "output"))
    )
    (net (code "94") (name "/~{CSYNC}") (class "Default")
      (node (ref "J1") (pin "P$1") (pinfunction "X1_P$1") (pintype "bidirectional"))
      (node (ref "U12") (pin "5") (pinfunction "5_5") (pintype "passive"))
      (node (ref "U14") (pin "4") (pinfunction "A_4") (pintype "input"))
      (node (ref "U7") (pin "45") (pinfunction "CSYNC_45") (pintype "bidirectional"))
    )
    (net (code "95") (name "/~{DBE}") (class "Default")
      (node (ref "U7") (pin "49") (pinfunction "DBE_49") (pintype "bidirectional"))
      (node (ref "U8") (pin "6") (pinfunction "6_6") (pintype "passive"))
    )
    (net (code "96") (name "/~{EXBE}") (class "Default")
      (node (ref "U7") (pin "50") (pinfunction "EXBE_50") (pintype "bidirectional"))
      (node (ref "U8") (pin "5") (pinfunction "5_5") (pintype "passive"))
    )
    (net (code "97") (name "/~{HALT}") (class "Default")
      (node (ref "J1") (pin "P$41") (pinfunction "X41_P$41") (pintype "bidirectional"))
      (node (ref "U1") (pin "18") (pinfunction "HALT_18") (pintype "output"))
    )
    (net (code "98") (name "/~{INT}") (class "Default")
      (node (ref "J1") (pin "P$3") (pinfunction "X3_P$3") (pintype "bidirectional"))
      (node (ref "R3") (pin "1") (pinfunction "1_1") (pintype "passive"))
      (node (ref "U1") (pin "16") (pinfunction "INT_16") (pintype "input"))
    )
    (net (code "99") (name "/~{IORQ}") (class "Default")
      (node (ref "J1") (pin "P$43") (pinfunction "X43_P$43") (pintype "bidirectional"))
      (node (ref "U1") (pin "20") (pinfunction "IORQ_20") (pintype "output"))
      (node (ref "U7") (pin "39") (pinfunction "IORQ_39") (pintype "bidirectional"))
      (node (ref "U8") (pin "17") (pinfunction "17_17") (pintype "passive"))
    )
    (net (code "100") (name "/~{KEY}") (class "Default")
      (node (ref "U7") (pin "11") (pinfunction "KEY_11") (pintype "bidirectional"))
      (node (ref "U9") (pin "1") (pinfunction "1G_1") (pintype "input"))
      (node (ref "U9") (pin "15") (pinfunction "2G_15") (pintype "input"))
    )
    (net (code "101") (name "/~{LAEB}") (class "Default")
      (node (ref "U7") (pin "51") (pinfunction "LAEB_51") (pintype "bidirectional"))
      (node (ref "U8") (pin "4") (pinfunction "4_4") (pintype "passive"))
    )
    (net (code "102") (name "/~{M1}") (class "Default")
      (node (ref "J1") (pin "P$6") (pinfunction "X6_P$6") (pintype "bidirectional"))
      (node (ref "U1") (pin "27") (pinfunction "M1_27") (pintype "output"))
    )
    (net (code "103") (name "/~{MREQ}") (class "Default")
      (node (ref "J1") (pin "P$38") (pinfunction "X38_P$38") (pintype "bidirectional"))
      (node (ref "U1") (pin "19") (pinfunction "MREQ_19") (pintype "output"))
      (node (ref "U11") (pin "5") (pinfunction "I2_5") (pintype "input"))
      (node (ref "U7") (pin "37") (pinfunction "MREQ_37") (pintype "bidirectional"))
    )
    (net (code "104") (name "/~{MRST}") (class "Default")
      (node (ref "C1") (pin "+") (pinfunction "+_+") (pintype "passive"))
      (node (ref "D1") (pin "A") (pinfunction "A_A") (pintype "passive"))
      (node (ref "D15") (pin "A") (pinfunction "A_A") (pintype "passive"))
      (node (ref "J1") (pin "P$5") (pinfunction "X5_P$5") (pintype "bidirectional"))
      (node (ref "J2") (pin "15") (pinfunction "15_15") (pintype "passive"))
      (node (ref "R5") (pin "1") (pinfunction "1_1") (pintype "passive"))
      (node (ref "U7") (pin "30") (pinfunction "MRST_30") (pintype "bidirectional"))
      (node (ref "U8") (pin "19") (pinfunction "19_19") (pintype "passive"))
    )
    (net (code "105") (name "/~{NMI}") (class "Default")
      (node (ref "J1") (pin "P$39") (pinfunction "X39_P$39") (pintype "bidirectional"))
      (node (ref "R1") (pin "1") (pinfunction "1_1") (pintype "passive"))
      (node (ref "U1") (pin "17") (pinfunction "NMI_17") (pintype "input"))
    )
    (net (code "106") (name "/~{RD}") (class "Default")
      (node (ref "J1") (pin "P$35") (pinfunction "X35_P$35") (pintype "bidirectional"))
      (node (ref "U1") (pin "21") (pinfunction "RD_21") (pintype "output"))
      (node (ref "U7") (pin "38") (pinfunction "RD_38") (pintype "bidirectional"))
    )
    (net (code "107") (name "/~{RFSH}") (class "Default")
      (node (ref "J1") (pin "P$7") (pinfunction "X7_P$7") (pintype "bidirectional"))
      (node (ref "U1") (pin "28") (pinfunction "RFSH_28") (pintype "output"))
    )
    (net (code "108") (name "/~{RM1}") (class "Default")
      (node (ref "U3") (pin "18") (pinfunction "~{CS}_18") (pintype "input"))
      (node (ref "U7") (pin "62") (pinfunction "RM1_62") (pintype "bidirectional"))
    )
    (net (code "109") (name "/~{RM2}") (class "Default")
      (node (ref "U4") (pin "18") (pinfunction "~{CS}_18") (pintype "input"))
      (node (ref "U7") (pin "61") (pinfunction "RM2_61") (pintype "bidirectional"))
    )
    (net (code "110") (name "/~{ROM}") (class "Default")
      (node (ref "U2") (pin "20") (pinfunction "20_20") (pintype "passive"))
      (node (ref "U7") (pin "10") (pinfunction "ROM_10") (pintype "bidirectional"))
    )
    (net (code "111") (name "/~{RST}") (class "Default")
      (node (ref "D15") (pin "C") (pinfunction "C_C") (pintype "passive"))
      (node (ref "R45") (pin "2") (pinfunction "2_2") (pintype "passive"))
      (node (ref "U1") (pin "26") (pinfunction "RESET_26") (pintype "input"))
    )
    (net (code "112") (name "/~{R{slash}W}") (class "Default")
      (node (ref "U3") (pin "21") (pinfunction "~{WE}_21") (pintype "input"))
      (node (ref "U4") (pin "21") (pinfunction "~{WE}_21") (pintype "input"))
      (node (ref "U7") (pin "52") (pinfunction "R/~{W}_52") (pintype "bidirectional"))
    )
    (net (code "113") (name "/~{WAIT}") (class "Default")
      (node (ref "J1") (pin "P$40") (pinfunction "X40_P$40") (pintype "bidirectional"))
      (node (ref "R25") (pin "1") (pinfunction "1_1") (pintype "passive"))
      (node (ref "U1") (pin "24") (pinfunction "WAIT_24") (pintype "input"))
      (node (ref "U7") (pin "35") (pinfunction "WAIT_35") (pintype "bidirectional"))
    )
    (net (code "114") (name "/~{WR}") (class "Default")
      (node (ref "J1") (pin "P$37") (pinfunction "X37_P$37") (pintype "bidirectional"))
      (node (ref "U1") (pin "22") (pinfunction "WR_22") (pintype "output"))
      (node (ref "U7") (pin "36") (pinfunction "WR_36") (pintype "bidirectional"))
      (node (ref "U8") (pin "18") (pinfunction "18_18") (pintype "passive"))
    )
    (net (code "115") (name "2Φ") (class "Default")
      (node (ref "R52") (pin "1") (pinfunction "1_1") (pintype "passive"))
      (node (ref "U11") (pin "12") (pinfunction "O_12") (pintype "output"))
      (node (ref "U6") (pin "2") (pinfunction "CLK_2") (pintype "input"))
      (node (ref "U7") (pin "2") (pinfunction "2Φ_2") (pintype "bidirectional"))
    )
    (net (code "116") (name "A14") (class "Default")
      (node (ref "D8") (pin "C") (pinfunction "C_C") (pintype "passive"))
      (node (ref "J1") (pin "P$10") (pinfunction "X10_P$10") (pintype "bidirectional"))
      (node (ref "U1") (pin "4") (pinfunction "A14_4") (pintype "output"))
      (node (ref "U11") (pin "10") (pinfunction "I1_10") (pintype "input"))
      (node (ref "U15") (pin "4") (pinfunction "I0_4") (pintype "input"))
    )
    (net (code "117") (name "A15") (class "Default")
      (node (ref "D9") (pin "C") (pinfunction "C_C") (pintype "passive"))
      (node (ref "J1") (pin "P$9") (pinfunction "X9_P$9") (pintype "bidirectional"))
      (node (ref "U1") (pin "5") (pinfunction "A15_5") (pintype "output"))
      (node (ref "U11") (pin "11") (pinfunction "I2_11") (pintype "input"))
      (node (ref "U15") (pin "10") (pinfunction "I1_10") (pintype "input"))
    )
    (net (code "118") (name "CASS.IN") (class "Default")
      (node (ref "Q1") (pin "1") (pinfunction "C_1") (pintype "passive"))
      (node (ref "R18") (pin "2") (pinfunction "2_2") (pintype "passive"))
      (node (ref "U7") (pin "42") (pinfunction "CASS.IN_42") (pintype "bidirectional"))
    )
    (net (code "119") (name "CASS.OUT") (class "Default")
      (node (ref "C30") (pin "-") (pinfunction "-_-") (pintype "passive"))
      (node (ref "R24") (pin "1") (pinfunction "1_1") (pintype "passive"))
      (node (ref "U7") (pin "43") (pinfunction "CASS.OUT_43") (pintype "bidirectional"))
    )
    (net (code "120") (name "COMP-LO") (class "Default")
      (node (ref "MOD1") (pin "1") (pinfunction "1_1") (pintype "passive"))
      (node (ref "R41") (pin "1") (pinfunction "1_1") (pintype "passive"))
      (node (ref "R42") (pin "1") (pinfunction "1_1") (pintype "passive"))
    )
    (net (code "121") (name "D00") (class "Default")
      (node (ref "U1") (pin "14") (pinfunction "D0_14") (pintype "bidirectional"))
      (node (ref "U2") (pin "9") (pinfunction "9_9") (pintype "passive"))
      (node (ref "U7") (pin "9") (pinfunction "D0_9") (pintype "bidirectional"))
      (node (ref "U8") (pin "9") (pinfunction "9_9") (pintype "passive"))
      (node (ref "U9") (pin "11") (pinfunction "2Y1_11") (pintype "tri_state"))
    )
    (net (code "122") (name "D01") (class "Default")
      (node (ref "U1") (pin "15") (pinfunction "D1_15") (pintype "bidirectional"))
      (node (ref "U2") (pin "10") (pinfunction "10_10") (pintype "passive"))
      (node (ref "U8") (pin "10") (pinfunction "10_10") (pintype "passive"))
      (node (ref "U9") (pin "5") (pinfunction "1Y2_5") (pintype "tri_state"))
    )
    (net (code "123") (name "D02") (class "Default")
      (node (ref "U1") (pin "12") (pinfunction "D2_12") (pintype "bidirectional"))
      (node (ref "U2") (pin "11") (pinfunction "11_11") (pintype "passive"))
      (node (ref "U8") (pin "11") (pinfunction "11_11") (pintype "passive"))
      (node (ref "U9") (pin "9") (pinfunction "1Y4_9") (pintype "tri_state"))
    )
    (net (code "124") (name "D03") (class "Default")
      (node (ref "U1") (pin "8") (pinfunction "D3_8") (pintype "bidirectional"))
      (node (ref "U2") (pin "13") (pinfunction "13_13") (pintype "passive"))
      (node (ref "U8") (pin "12") (pinfunction "12_12") (pintype "passive"))
      (node (ref "U9") (pin "13") (pinfunction "2Y2_13") (pintype "tri_state"))
    )
    (net (code "125") (name "D04") (class "Default")
      (node (ref "U1") (pin "7") (pinfunction "D4_7") (pintype "bidirectional"))
      (node (ref "U2") (pin "14") (pinfunction "14_14") (pintype "passive"))
      (node (ref "U8") (pin "13") (pinfunction "13_13") (pintype "passive"))
      (node (ref "U9") (pin "3") (pinfunction "1Y1_3") (pintype "tri_state"))
    )
    (net (code "126") (name "D05") (class "Default")
      (node (ref "U1") (pin "9") (pinfunction "D5_9") (pintype "bidirectional"))
      (node (ref "U2") (pin "15") (pinfunction "15_15") (pintype "passive"))
      (node (ref "U8") (pin "14") (pinfunction "14_14") (pintype "passive"))
      (node (ref "U9") (pin "7") (pinfunction "1Y3_7") (pintype "tri_state"))
    )
    (net (code "127") (name "GND") (class "Default")
      (node (ref "C1") (pin "-") (pinfunction "-_-") (pintype "passive"))
      (node (ref "C10") (pin "1") (pinfunction "1_1") (pintype "passive"))
      (node (ref "C11") (pin "2") (pinfunction "2_2") (pintype "passive"))
      (node (ref "C12") (pin "-") (pinfunction "-_-") (pintype "passive"))
      (node (ref "C13") (pin "+") (pinfunction "+_+") (pintype "passive"))
      (node (ref "C15") (pin "2") (pinfunction "2_2") (pintype "passive"))
      (node (ref "C16") (pin "1") (pinfunction "1_1") (pintype "passive"))
      (node (ref "C17") (pin "2") (pinfunction "2_2") (pintype "passive"))
      (node (ref "C18") (pin "1") (pinfunction "1_1") (pintype "passive"))
      (node (ref "C19") (pin "1") (pinfunction "1_1") (pintype "passive"))
      (node (ref "C20") (pin "2") (pinfunction "2_2") (pintype "passive"))
      (node (ref "C21") (pin "2") (pinfunction "2_2") (pintype "passive"))
      (node (ref "C22") (pin "2") (pinfunction "2_2") (pintype "passive"))
      (node (ref "C24") (pin "2") (pinfunction "2_2") (pintype "passive"))
      (node (ref "C25") (pin "2") (pinfunction "2_2") (pintype "passive"))
      (node (ref "C26") (pin "2") (pinfunction "2_2") (pintype "passive"))
      (node (ref "C27") (pin "2") (pinfunction "2_2") (pintype "passive"))
      (node (ref "C28") (pin "1") (pinfunction "1_1") (pintype "passive"))
      (node (ref "C29") (pin "1") (pinfunction "1_1") (pintype "passive"))
      (node (ref "C3") (pin "2") (pinfunction "2_2") (pintype "passive"))
      (node (ref "C31") (pin "1") (pinfunction "1_1") (pintype "passive"))
      (node (ref "C33") (pin "1") (pinfunction "1_1") (pintype "passive"))
      (node (ref "C35") (pin "2") (pinfunction "2_2") (pintype "passive"))
      (node (ref "C36") (pin "1") (pinfunction "1_1") (pintype "passive"))
      (node (ref "C38") (pin "1") (pinfunction "1_1") (pintype "passive"))
      (node (ref "C40") (pin "2") (pinfunction "2_2") (pintype "passive"))
      (node (ref "C41") (pin "2") (pinfunction "2_2") (pintype "passive"))
      (node (ref "C42") (pin "2") (pinfunction "2_2") (pintype "passive"))
      (node (ref "C43") (pin "2") (pinfunction "2_2") (pintype "passive"))
      (node (ref "C6") (pin "-") (pinfunction "-_-") (pintype "passive"))
      (node (ref "C7") (pin "1") (pinfunction "1_1") (pintype "passive"))
      (node (ref "C8") (pin "-") (pinfunction "-_-") (pintype "passive"))
      (node (ref "C9") (pin "-") (pinfunction "-_-") (pintype "passive"))
      (node (ref "D10") (pin "A") (pinfunction "A_A") (pintype "passive"))
      (node (ref "D11") (pin "A") (pinfunction "A_A") (pintype "passive"))
      (node (ref "D12") (pin "A") (pinfunction "A_A") (pintype "passive"))
      (node (ref "D13") (pin "A") (pinfunction "A_A") (pintype "passive"))
      (node (ref "D16") (pin "A") (pinfunction "A_A") (pintype "passive"))
      (node (ref "F1") (pin "0") (pinfunction "GND_0") (pintype "power_in"))
      (node (ref "F2") (pin "2") (pinfunction "2_2") (pintype "passive"))
      (node (ref "F3") (pin "0") (pinfunction "GND_0") (pintype "power_in"))
      (node (ref "J1") (pin "P$34") (pinfunction "X34_P$34") (pintype "bidirectional"))
      (node (ref "J1") (pin "P$44") (pinfunction "X44_P$44") (pintype "bidirectional"))
      (node (ref "J2") (pin "16") (pinfunction "16_16") (pintype "passive"))
      (node (ref "J4") (pin "SLEEVE") (pinfunction "SLEEVE_SLEEVE") (pintype "bidirectional"))
      (node (ref "J5") (pin "2") (pinfunction "2_2") (pintype "bidirectional"))
      (node (ref "LED1") (pin "K") (pinfunction "C_K") (pintype "passive"))
      (node (ref "Q1") (pin "3") (pinfunction "E_3") (pintype "passive"))
      (node (ref "Q5") (pin "3") (pinfunction "E_3") (pintype "passive"))
      (node (ref "Q8") (pin "3") (pinfunction "E_3") (pintype "passive"))
      (node (ref "R15") (pin "2") (pinfunction "2_2") (pintype "passive"))
      (node (ref "R20") (pin "1") (pinfunction "1_1") (pintype "passive"))
      (node (ref "R22") (pin "1") (pinfunction "1_1") (pintype "passive"))
      (node (ref "R23") (pin "1") (pinfunction "1_1") (pintype "passive"))
      (node (ref "R30") (pin "1") (pinfunction "1_1") (pintype "passive"))
      (node (ref "R33") (pin "2") (pinfunction "2_2") (pintype "passive"))
      (node (ref "R38") (pin "2") (pinfunction "2_2") (pintype "passive"))
      (node (ref "R39") (pin "2") (pinfunction "2_2") (pintype "passive"))
      (node (ref "R41") (pin "2") (pinfunction "2_2") (pintype "passive"))
      (node (ref "R44") (pin "2") (pinfunction "2_2") (pintype "passive"))
      (node (ref "R45") (pin "1") (pinfunction "1_1") (pintype "passive"))
      (node (ref "R49") (pin "1") (pinfunction "1_1") (pintype "passive"))
      (node (ref "R53") (pin "1") (pinfunction "1_1") (pintype "passive"))
      (node (ref "R55") (pin "1") (pinfunction "1_1") (pintype "passive"))
      (node (ref "SW2") (pin "3") (pinfunction "O_3") (pintype "passive"))
      (node (ref "TR1") (pin "P$3") (pinfunction "S_P$3") (pintype "passive"))
      (node (ref "TR1") (pin "P$4") (pinfunction "S_P$4") (pintype "passive"))
      (node (ref "U1") (pin "29") (pinfunction "GND_29") (pintype "power_in"))
      (node (ref "U10") (pin "2") (pinfunction "GND_2") (pintype "passive"))
      (node (ref "U12") (pin "16") (pinfunction "16_16") (pintype "passive"))
      (node (ref "U14") (pin "1") (pinfunction "T1_1") (pintype "input"))
      (node (ref "U2") (pin "12") (pinfunction "12_12") (pintype "passive"))
      (node (ref "U3") (pin "20") (pinfunction "~{OE}_20") (pintype "input"))
      (node (ref "U4") (pin "20") (pinfunction "~{OE}_20") (pintype "input"))
      (node (ref "U5") (pin "12") (pinfunction "12_12") (pintype "passive"))
      (node (ref "U5") (pin "18") (pinfunction "18_18") (pintype "passive"))
      (node (ref "U7") (pin "1") (pinfunction "GND_1") (pintype "power_in"))
      (node (ref "U7") (pin "33") (pinfunction "P33_33") (pintype "bidirectional"))
      (node (ref "U8") (pin "1") (pinfunction "1_1") (pintype "passive"))
      (node (ref "ZD1") (pin "A") (pinfunction "A_A") (pintype "passive"))
    )
    (net (code "128") (name "Net-(C4-Pad1)") (class "Default")
      (node (ref "C4") (pin "1") (pinfunction "1_1") (pintype "passive"))
      (node (ref "J5") (pin "3") (pinfunction "3_3") (pintype "bidirectional"))
      (node (ref "R39") (pin "1") (pinfunction "1_1") (pintype "passive"))
    )
    (net (code "129") (name "Net-(C5-Pad-)") (class "Default")
      (node (ref "C5") (pin "-") (pinfunction "-_-") (pintype "passive"))
      (node (ref "R16") (pin "1") (pinfunction "1_1") (pintype "passive"))
    )
    (net (code "130") (name "Net-(C8-Pad+)") (class "Default")
      (node (ref "C8") (pin "+") (pinfunction "+_+") (pintype "passive"))
      (node (ref "F3") (pin "2") (pinfunction "2_2") (pintype "passive"))
      (node (ref "SW1") (pin "P$2A") (pinfunction "P$2A_P$2A") (pintype "bidirectional"))
      (node (ref "SW1") (pin "P$2B") (pinfunction "P$2B_P$2B") (pintype "bidirectional"))
    )
    (net (code "131") (name "Net-(C11-Pad1)") (class "Default")
      (node (ref "C11") (pin "1") (pinfunction "1_1") (pintype "passive"))
      (node (ref "L5") (pin "2") (pinfunction "2_2") (pintype "passive"))
      (node (ref "R48") (pin "2") (pinfunction "2_2") (pintype "passive"))
    )
    (net (code "132") (name "Net-(C13-Pad-)") (class "Default")
      (node (ref "C13") (pin "-") (pinfunction "-_-") (pintype "passive"))
      (node (ref "R48") (pin "1") (pinfunction "1_1") (pintype "passive"))
      (node (ref "SW1") (pin "P$3A") (pinfunction "P$3A_P$3A") (pintype "bidirectional"))
      (node (ref "SW1") (pin "P$3B") (pinfunction "P$3B_P$3B") (pintype "bidirectional"))
    )
    (net (code "133") (name "Net-(C14-Pad1)") (class "Default")
      (node (ref "C14") (pin "1") (pinfunction "1_1") (pintype "passive"))
      (node (ref "U12") (pin "11") (pinfunction "11_11") (pintype "passive"))
    )
    (net (code "134") (name "Net-(C16-Pad2)") (class "Default")
      (node (ref "C16") (pin "2") (pinfunction "2_2") (pintype "passive"))
      (node (ref "L3") (pin "1") (pinfunction "1_1") (pintype "passive"))
      (node (ref "L4") (pin "1") (pinfunction "1_1") (pintype "passive"))
    )
    (net (code "135") (name "Net-(C18-Pad2)") (class "Default")
      (node (ref "C18") (pin "2") (pinfunction "2_2") (pintype "passive"))
      (node (ref "L2") (pin "1") (pinfunction "1_1") (pintype "passive"))
      (node (ref "L3") (pin "2") (pinfunction "2_2") (pintype "passive"))
    )
    (net (code "136") (name "Net-(C19-Pad2)") (class "Default")
      (node (ref "C19") (pin "2") (pinfunction "2_2") (pintype "passive"))
      (node (ref "L1") (pin "1") (pinfunction "1_1") (pintype "passive"))
      (node (ref "L2") (pin "2") (pinfunction "2_2") (pintype "passive"))
    )
    (net (code "137") (name "Net-(C23-Pad2)") (class "Default")
      (node (ref "C23") (pin "2") (pinfunction "2_2") (pintype "passive"))
      (node (ref "XTAL2") (pin "2") (pinfunction "2_2") (pintype "passive"))
    )
    (net (code "138") (name "Net-(C29-Pad2)") (class "Default")
      (node (ref "C29") (pin "2") (pinfunction "2_2") (pintype "passive"))
      (node (ref "R33") (pin "1") (pinfunction "1_1") (pintype "passive"))
      (node (ref "U12") (pin "17") (pinfunction "17_17") (pintype "passive"))
    )
    (net (code "139") (name "Net-(C30-Pad+)") (class "Default")
      (node (ref "C30") (pin "+") (pinfunction "+_+") (pintype "passive"))
      (node (ref "R43") (pin "1") (pinfunction "1_1") (pintype "passive"))
    )
    (net (code "140") (name "Net-(C31-Pad2)") (class "Default")
      (node (ref "C31") (pin "2") (pinfunction "2_2") (pintype "passive"))
      (node (ref "R35") (pin "2") (pinfunction "2_2") (pintype "passive"))
      (node (ref "R53") (pin "2") (pinfunction "2_2") (pintype "passive"))
      (node (ref "R54") (pin "2") (pinfunction "2_2") (pintype "passive"))
    )
    (net (code "141") (name "Net-(CT1-A)") (class "Default")
      (node (ref "CT1") (pin "2") (pinfunction "A_2") (pintype "passive"))
      (node (ref "U12") (pin "14") (pinfunction "14_14") (pintype "passive"))
    )
    (net (code "142") (name "Net-(CT1-E)") (class "Default")
      (node (ref "C34") (pin "1") (pinfunction "1_1") (pintype "passive"))
      (node (ref "CT1") (pin "1") (pinfunction "E_1") (pintype "passive"))
      (node (ref "XTAL1") (pin "1") (pinfunction "1_1") (pintype "passive"))
    )
    (net (code "143") (name "Net-(D2-PadA)") (class "Default")
      (node (ref "D2") (pin "A") (pinfunction "A_A") (pintype "passive"))
      (node (ref "J2") (pin "1") (pinfunction "1_1") (pintype "passive"))
    )
    (net (code "144") (name "Net-(D3-PadA)") (class "Default")
      (node (ref "D3") (pin "A") (pinfunction "A_A") (pintype "passive"))
      (node (ref "J2") (pin "2") (pinfunction "2_2") (pintype "passive"))
    )
    (net (code "145") (name "Net-(D4-PadA)") (class "Default")
      (node (ref "D4") (pin "A") (pinfunction "A_A") (pintype "passive"))
      (node (ref "J2") (pin "3") (pinfunction "3_3") (pintype "passive"))
    )
    (net (code "146") (name "Net-(D5-PadA)") (class "Default")
      (node (ref "D5") (pin "A") (pinfunction "A_A") (pintype "passive"))
      (node (ref "J2") (pin "4") (pinfunction "4_4") (pintype "passive"))
    )
    (net (code "147") (name "Net-(D6-PadA)") (class "Default")
      (node (ref "D6") (pin "A") (pinfunction "A_A") (pintype "passive"))
      (node (ref "J2") (pin "5") (pinfunction "5_5") (pintype "passive"))
    )
    (net (code "148") (name "Net-(D7-PadA)") (class "Default")
      (node (ref "D7") (pin "A") (pinfunction "A_A") (pintype "passive"))
      (node (ref "J2") (pin "6") (pinfunction "6_6") (pintype "passive"))
    )
    (net (code "149") (name "Net-(D8-PadA)") (class "Default")
      (node (ref "D8") (pin "A") (pinfunction "A_A") (pintype "passive"))
      (node (ref "J2") (pin "7") (pinfunction "7_7") (pintype "passive"))
    )
    (net (code "150") (name "Net-(D9-PadA)") (class "Default")
      (node (ref "D9") (pin "A") (pinfunction "A_A") (pintype "passive"))
      (node (ref "J2") (pin "8") (pinfunction "8_8") (pintype "passive"))
    )
    (net (code "151") (name "Net-(F1-Pad1)") (class "Default")
      (node (ref "F1") (pin "1") (pinfunction "1_1") (pintype "passive"))
      (node (ref "L6") (pin "2") (pinfunction "2_2") (pintype "passive"))
    )
    (net (code "152") (name "Net-(F2-GND)") (class "Default")
      (node (ref "C9") (pin "+") (pinfunction "+_+") (pintype "passive"))
      (node (ref "F1") (pin "2") (pinfunction "2_2") (pintype "passive"))
      (node (ref "F2") (pin "0") (pinfunction "GND_0") (pintype "power_in"))
      (node (ref "SW1") (pin "P$1A") (pinfunction "P$1A_P$1A") (pintype "bidirectional"))
      (node (ref "SW1") (pin "P$1B") (pinfunction "P$1B_P$1B") (pintype "bidirectional"))
    )
    (net (code "153") (name "Net-(F2-Pad1)") (class "Default")
      (node (ref "F2") (pin "1") (pinfunction "1_1") (pintype "passive"))
      (node (ref "L7") (pin "2") (pinfunction "2_2") (pintype "passive"))
    )
    (net (code "154") (name "Net-(F3-Pad1)") (class "Default")
      (node (ref "F3") (pin "1") (pinfunction "1_1") (pintype "passive"))
      (node (ref "L8") (pin "2") (pinfunction "2_2") (pintype "passive"))
    )
    (net (code "155") (name "Net-(J4-PadRING)") (class "Default")
      (node (ref "J4") (pin "RING") (pinfunction "RING_RING") (pintype "bidirectional"))
      (node (ref "J4") (pin "RSH") (pinfunction "RSH_RSH") (pintype "bidirectional"))
      (node (ref "R31") (pin "1") (pinfunction "1_1") (pintype "passive"))
    )
    (net (code "156") (name "Net-(J4-PadTIP)") (class "Default")
      (node (ref "J4") (pin "TIP") (pinfunction "TIP_TIP") (pintype "bidirectional"))
      (node (ref "J4") (pin "TSH") (pinfunction "TSH_TSH") (pintype "bidirectional"))
      (node (ref "R29") (pin "1") (pinfunction "1_1") (pintype "passive"))
    )
    (net (code "157") (name "Net-(J5-Pad1)") (class "Default")
      (node (ref "J5") (pin "1") (pinfunction "1_1") (pintype "bidirectional"))
      (node (ref "R23") (pin "2") (pinfunction "2_2") (pintype "passive"))
      (node (ref "R24") (pin "2") (pinfunction "2_2") (pintype "passive"))
    )
    (net (code "158") (name "Net-(L1-Pad2)") (class "Default")
      (node (ref "L1") (pin "2") (pinfunction "2_2") (pintype "passive"))
      (node (ref "R38") (pin "1") (pinfunction "1_1") (pintype "passive"))
      (node (ref "U12") (pin "7") (pinfunction "7_7") (pintype "passive"))
    )
    (net (code "159") (name "Net-(L4-Pad2)") (class "Default")
      (node (ref "L4") (pin "2") (pinfunction "2_2") (pintype "passive"))
      (node (ref "R32") (pin "1") (pinfunction "1_1") (pintype "passive"))
    )
    (net (code "160") (name "Net-(LED1-PadA)") (class "Default")
      (node (ref "LED1") (pin "A") (pinfunction "A_A") (pintype "passive"))
      (node (ref "R46") (pin "1") (pinfunction "1_1") (pintype "passive"))
    )
    (net (code "161") (name "Net-(MOD2-Pad1)") (class "Default")
      (node (ref "MOD2") (pin "1") (pinfunction "1_1") (pintype "passive"))
      (node (ref "R40") (pin "1") (pinfunction "1_1") (pintype "passive"))
    )
    (net (code "162") (name "Net-(Q1-B)") (class "Default")
      (node (ref "D11") (pin "C") (pinfunction "C_C") (pintype "passive"))
      (node (ref "Q1") (pin "2") (pinfunction "B_2") (pintype "passive"))
      (node (ref "R16") (pin "2") (pinfunction "2_2") (pintype "passive"))
      (node (ref "R17") (pin "2") (pinfunction "2_2") (pintype "passive"))
    )
    (net (code "163") (name "Net-(Q2-B)") (class "Default")
      (node (ref "C4") (pin "2") (pinfunction "2_2") (pintype "passive"))
      (node (ref "D12") (pin "C") (pinfunction "C_C") (pintype "passive"))
      (node (ref "Q2") (pin "2") (pinfunction "B_2") (pintype "passive"))
      (node (ref "R21") (pin "2") (pinfunction "2_2") (pintype "passive"))
      (node (ref "R22") (pin "2") (pinfunction "2_2") (pintype "passive"))
    )
    (net (code "164") (name "Net-(Q2-C)") (class "Default")
      (node (ref "C5") (pin "+") (pinfunction "+_+") (pintype "passive"))
      (node (ref "Q2") (pin "1") (pinfunction "C_1") (pintype "passive"))
      (node (ref "R19") (pin "2") (pinfunction "2_2") (pintype "passive"))
    )
    (net (code "165") (name "Net-(Q2-E)") (class "Default")
      (node (ref "Q2") (pin "3") (pinfunction "E_3") (pintype "passive"))
      (node (ref "R20") (pin "2") (pinfunction "2_2") (pintype "passive"))
    )
    (net (code "166") (name "Net-(Q3-B)") (class "Default")
      (node (ref "Q3") (pin "2") (pinfunction "B_2") (pintype "passive"))
      (node (ref "R27") (pin "1") (pinfunction "1_1") (pintype "passive"))
      (node (ref "R36") (pin "2") (pinfunction "2_2") (pintype "passive"))
    )
    (net (code "167") (name "Net-(Q3-C)") (class "Default")
      (node (ref "Q3") (pin "1") (pinfunction "C_1") (pintype "passive"))
      (node (ref "R28") (pin "1") (pinfunction "1_1") (pintype "passive"))
      (node (ref "R29") (pin "2") (pinfunction "2_2") (pintype "passive"))
    )
    (net (code "168") (name "Net-(Q4-B)") (class "Default")
      (node (ref "C7") (pin "2") (pinfunction "2_2") (pintype "passive"))
      (node (ref "Q4") (pin "1") (pinfunction "B_1") (pintype "passive"))
      (node (ref "R37") (pin "1") (pinfunction "1_1") (pintype "passive"))
      (node (ref "ZD1") (pin "C") (pinfunction "C_C") (pintype "passive"))
    )
    (net (code "169") (name "Net-(Q4-C)") (class "Default")
      (node (ref "Q4") (pin "2") (pinfunction "C_2") (pintype "passive"))
      (node (ref "R37") (pin "2") (pinfunction "2_2") (pintype "passive"))
      (node (ref "SW1") (pin "P$2C") (pinfunction "P$2C_P$2C") (pintype "bidirectional"))
    )
    (net (code "170") (name "Net-(Q5-B)") (class "Default")
      (node (ref "C2") (pin "2") (pinfunction "2_2") (pintype "passive"))
      (node (ref "D10") (pin "C") (pinfunction "C_C") (pintype "passive"))
      (node (ref "Q5") (pin "2") (pinfunction "B_2") (pintype "passive"))
      (node (ref "R15") (pin "1") (pinfunction "1_1") (pintype "passive"))
    )
    (net (code "171") (name "Net-(Q5-C)") (class "Default")
      (node (ref "Q5") (pin "1") (pinfunction "C_1") (pintype "passive"))
      (node (ref "R14") (pin "2") (pinfunction "2_2") (pintype "passive"))
      (node (ref "U6") (pin "1") (pinfunction "SH/~{LD}_1") (pintype "input"))
    )
    (net (code "172") (name "Net-(Q6-B)") (class "Default")
      (node (ref "Q6") (pin "2") (pinfunction "B_2") (pintype "passive"))
      (node (ref "R34") (pin "2") (pinfunction "2_2") (pintype "passive"))
      (node (ref "R35") (pin "1") (pinfunction "1_1") (pintype "passive"))
    )
    (net (code "173") (name "Net-(Q6-C)") (class "Default")
      (node (ref "C39") (pin "1") (pinfunction "1_1") (pintype "passive"))
      (node (ref "Q6") (pin "1") (pinfunction "C_1") (pintype "passive"))
      (node (ref "R60") (pin "1") (pinfunction "1_1") (pintype "passive"))
    )
    (net (code "174") (name "Net-(Q6-E)") (class "Default")
      (node (ref "Q6") (pin "3") (pinfunction "E_3") (pintype "passive"))
      (node (ref "R44") (pin "1") (pinfunction "1_1") (pintype "passive"))
      (node (ref "R59") (pin "2") (pinfunction "2_2") (pintype "passive"))
      (node (ref "U16") (pin "2") (pinfunction "B_2") (pintype "passive"))
    )
    (net (code "175") (name "Net-(Q7-B)") (class "Default")
      (node (ref "Q7") (pin "2") (pinfunction "B_2") (pintype "passive"))
      (node (ref "U16") (pin "1") (pinfunction "A_1") (pintype "passive"))
      (node (ref "U16") (pin "11") (pinfunction "A_11") (pintype "passive"))
    )
    (net (code "176") (name "Net-(Q7-E)") (class "Default")
      (node (ref "Q7") (pin "3") (pinfunction "E_3") (pintype "passive"))
      (node (ref "R42") (pin "2") (pinfunction "2_2") (pintype "passive"))
    )
    (net (code "177") (name "Net-(Q8-B)") (class "Default")
      (node (ref "C34") (pin "2") (pinfunction "2_2") (pintype "passive"))
      (node (ref "Q8") (pin "2") (pinfunction "B_2") (pintype "passive"))
      (node (ref "R56") (pin "1") (pinfunction "1_1") (pintype "passive"))
    )
    (net (code "178") (name "Net-(Q8-C)") (class "Default")
      (node (ref "C37") (pin "2") (pinfunction "2_2") (pintype "passive"))
      (node (ref "Q8") (pin "1") (pinfunction "C_1") (pintype "passive"))
      (node (ref "R56") (pin "2") (pinfunction "2_2") (pintype "passive"))
      (node (ref "R57") (pin "1") (pinfunction "1_1") (pintype "passive"))
    )
    (net (code "179") (name "Net-(R26-Pad2)") (class "Default")
      (node (ref "R26") (pin "2") (pinfunction "2_2") (pintype "passive"))
      (node (ref "U12") (pin "9") (pinfunction "9_9") (pintype "passive"))
    )
    (net (code "180") (name "Net-(R32-Pad2)") (class "Default")
      (node (ref "R32") (pin "2") (pinfunction "2_2") (pintype "passive"))
      (node (ref "U12") (pin "6") (pinfunction "6_6") (pintype "passive"))
    )
    (net (code "181") (name "Net-(R34-Pad1)") (class "Default")
      (node (ref "R34") (pin "1") (pinfunction "1_1") (pintype "passive"))
      (node (ref "U12") (pin "8") (pinfunction "8_8") (pintype "passive"))
    )
    (net (code "182") (name "Net-(R36-Pad1)") (class "Default")
      (node (ref "R36") (pin "1") (pinfunction "1_1") (pintype "passive"))
      (node (ref "ZD2") (pin "C") (pinfunction "C_C") (pintype "passive"))
    )
    (net (code "183") (name "Net-(SW2-P)") (class "Default")
      (node (ref "C36") (pin "2") (pinfunction "2_2") (pintype "passive"))
      (node (ref "MOD4") (pin "1") (pinfunction "1_1") (pintype "passive"))
      (node (ref "SW2") (pin "2") (pinfunction "P_2") (pintype "passive"))
    )
    (net (code "184") (name "Net-(TR1-E)") (class "Default")
      (node (ref "C14") (pin "2") (pinfunction "2_2") (pintype "passive"))
      (node (ref "C32") (pin "2") (pinfunction "2_2") (pintype "passive"))
      (node (ref "TR1") (pin "P$2") (pinfunction "E_P$2") (pintype "passive"))
    )
    (net (code "185") (name "Net-(U7-PALSW)") (class "Default")
      (node (ref "JP1") (pin "1") (pinfunction "1_1") (pintype "passive"))
      (node (ref "U7") (pin "48") (pinfunction "PALSW_48") (pintype "bidirectional"))
    )
    (net (code "186") (name "Net-(U7-PALSW2)") (class "Default")
      (node (ref "JP2") (pin "1") (pinfunction "1_1") (pintype "passive"))
      (node (ref "U7") (pin "34") (pinfunction "PALSW2_34") (pintype "bidirectional"))
    )
    (net (code "187") (name "Net-(U7-~{525}{slash}625)") (class "Default")
      (node (ref "R49") (pin "2") (pinfunction "2_2") (pintype "passive"))
      (node (ref "U7") (pin "13") (pinfunction "~{525}/625_13") (pintype "bidirectional"))
    )
    (net (code "188") (name "Net-(U9A-1A1)") (class "Default")
      (node (ref "J2") (pin "9") (pinfunction "9_9") (pintype "passive"))
      (node (ref "RA1") (pin "2") (pinfunction "2_2") (pintype "passive"))
      (node (ref "U9") (pin "2") (pinfunction "1A1_2") (pintype "input"))
    )
    (net (code "189") (name "Net-(U9A-1A2)") (class "Default")
      (node (ref "J2") (pin "11") (pinfunction "11_11") (pintype "passive"))
      (node (ref "RA1") (pin "4") (pinfunction "4_4") (pintype "passive"))
      (node (ref "U9") (pin "4") (pinfunction "1A2_4") (pintype "input"))
    )
    (net (code "190") (name "Net-(U9A-1A3)") (class "Default")
      (node (ref "J2") (pin "13") (pinfunction "13_13") (pintype "passive"))
      (node (ref "RA1") (pin "6") (pinfunction "6_6") (pintype "passive"))
      (node (ref "U9") (pin "6") (pinfunction "1A3_6") (pintype "input"))
    )
    (net (code "191") (name "Net-(U9A-1A4)") (class "Default")
      (node (ref "J2") (pin "14") (pinfunction "14_14") (pintype "passive"))
      (node (ref "RA1") (pin "7") (pinfunction "7_7") (pintype "passive"))
      (node (ref "U9") (pin "10") (pinfunction "1A4_10") (pintype "input"))
    )
    (net (code "192") (name "Net-(U9A-2A1)") (class "Default")
      (node (ref "J2") (pin "12") (pinfunction "12_12") (pintype "passive"))
      (node (ref "RA1") (pin "5") (pinfunction "5_5") (pintype "passive"))
      (node (ref "U9") (pin "12") (pinfunction "2A1_12") (pintype "input"))
    )
    (net (code "193") (name "Net-(U9A-2A2)") (class "Default")
      (node (ref "J2") (pin "10") (pinfunction "10_10") (pintype "passive"))
      (node (ref "RA1") (pin "3") (pinfunction "3_3") (pintype "passive"))
      (node (ref "U9") (pin "14") (pinfunction "2A2_14") (pintype "input"))
    )
    (net (code "194") (name "Net-(U10-VI)") (class "Default")
      (node (ref "C3") (pin "1") (pinfunction "1_1") (pintype "passive"))
      (node (ref "R46") (pin "2") (pinfunction "2_2") (pintype "passive"))
      (node (ref "SW1") (pin "P$1C") (pinfunction "P$1C_P$1C") (pintype "bidirectional"))
      (node (ref "U10") (pin "1") (pinfunction "VI_1") (pintype "input"))
    )
    (net (code "195") (name "Net-(U11A-I1)") (class "Default")
      (node (ref "C37") (pin "1") (pinfunction "1_1") (pintype "passive"))
      (node (ref "D16") (pin "C") (pinfunction "C_C") (pintype "passive"))
      (node (ref "R55") (pin "2") (pinfunction "2_2") (pintype "passive"))
      (node (ref "U11") (pin "2") (pinfunction "I1_2") (pintype "input"))
    )
    (net (code "196") (name "Net-(U11B-I0)") (class "Default")
      (node (ref "U11") (pin "3") (pinfunction "I0_3") (pintype "input"))
      (node (ref "U11") (pin "4") (pinfunction "I1_4") (pintype "input"))
    )
    (net (code "197") (name "Net-(U11B-O)") (class "Default")
      (node (ref "U11") (pin "6") (pinfunction "O_6") (pintype "output"))
      (node (ref "U11") (pin "9") (pinfunction "I0_9") (pintype "input"))
    )
    (net (code "198") (name "Net-(U12-Pad13)") (class "Default")
      (node (ref "U12") (pin "13") (pinfunction "13_13") (pintype "passive"))
      (node (ref "XTAL1") (pin "2") (pinfunction "2_2") (pintype "passive"))
    )
    (net (code "199") (name "Net-(U13A-I)") (class "Default")
      (node (ref "C23") (pin "1") (pinfunction "1_1") (pintype "passive"))
      (node (ref "R50") (pin "2") (pinfunction "2_2") (pintype "passive"))
      (node (ref "U13") (pin "1") (pinfunction "I_1") (pintype "input"))
    )
    (net (code "200") (name "Net-(U13A-O)") (class "Default")
      (node (ref "R50") (pin "1") (pinfunction "1_1") (pintype "passive"))
      (node (ref "R51") (pin "1") (pinfunction "1_1") (pintype "passive"))
      (node (ref "U13") (pin "2") (pinfunction "O_2") (pintype "output"))
      (node (ref "U13") (pin "3") (pinfunction "I_3") (pintype "input"))
    )
    (net (code "201") (name "Net-(U13B-O)") (class "Default")
      (node (ref "R51") (pin "2") (pinfunction "2_2") (pintype "passive"))
      (node (ref "U13") (pin "4") (pinfunction "O_4") (pintype "output"))
      (node (ref "U13") (pin "5") (pinfunction "I_5") (pintype "input"))
      (node (ref "XTAL2") (pin "1") (pinfunction "1_1") (pintype "passive"))
    )
    (net (code "202") (name "Net-(U13C-O)") (class "Default")
      (node (ref "R52") (pin "2") (pinfunction "2_2") (pintype "passive"))
      (node (ref "U13") (pin "6") (pinfunction "O_6") (pintype "output"))
    )
    (net (code "203") (name "Net-(U14A-Q)") (class "Default")
      (node (ref "U14") (pin "6") (pinfunction "Q_6") (pintype "output"))
      (node (ref "U16") (pin "12") (pinfunction "C_12") (pintype "input"))
    )
    (net (code "204") (name "Net-(U14A-T2)") (class "Default")
      (node (ref "C33") (pin "2") (pinfunction "2_2") (pintype "passive"))
      (node (ref "R58") (pin "1") (pinfunction "1_1") (pintype "passive"))
      (node (ref "U14") (pin "2") (pinfunction "T2_2") (pintype "input"))
    )
    (net (code "205") (name "Net-(U14A-~{Q})") (class "Default")
      (node (ref "U14") (pin "7") (pinfunction "~{Q}_7") (pintype "output"))
      (node (ref "U16") (pin "13") (pinfunction "C_13") (pintype "input"))
    )
    (net (code "206") (name "Net-(U16D-B)") (class "Default")
      (node (ref "C39") (pin "2") (pinfunction "2_2") (pintype "passive"))
      (node (ref "R59") (pin "1") (pinfunction "1_1") (pintype "passive"))
      (node (ref "U16") (pin "10") (pinfunction "B_10") (pintype "passive"))
    )
    (net (code "207") (name "PIN-8.8VDC") (class "Default")
      (node (ref "C40") (pin "1") (pinfunction "1_1") (pintype "passive"))
      (node (ref "J3") (pin "3") (pinfunction "3_3") (pintype "bidirectional"))
      (node (ref "L6") (pin "1") (pinfunction "1_1") (pintype "passive"))
    )
    (net (code "208") (name "PIN-16VDC") (class "Default")
      (node (ref "C42") (pin "1") (pinfunction "1_1") (pintype "passive"))
      (node (ref "J3") (pin "4") (pinfunction "4_4") (pintype "bidirectional"))
      (node (ref "L5") (pin "1") (pinfunction "1_1") (pintype "passive"))
    )
    (net (code "209") (name "PIN-19VDC") (class "Default")
      (node (ref "C41") (pin "1") (pinfunction "1_1") (pintype "passive"))
      (node (ref "J3") (pin "1") (pinfunction "1_1") (pintype "bidirectional"))
      (node (ref "L8") (pin "1") (pinfunction "1_1") (pintype "passive"))
    )
    (net (code "210") (name "PIN-GND") (class "Default")
      (node (ref "J3") (pin "2") (pinfunction "2_2") (pintype "bidirectional"))
      (node (ref "L7") (pin "1") (pinfunction "1_1") (pintype "passive"))
    )
    (net (code "211") (name "SND") (class "Default")
      (node (ref "J1") (pin "P$2") (pinfunction "X2_P$2") (pintype "bidirectional"))
      (node (ref "MOD3") (pin "1") (pinfunction "1_1") (pintype "passive"))
      (node (ref "R43") (pin "2") (pinfunction "2_2") (pintype "passive"))
      (node (ref "R47") (pin "1") (pinfunction "1_1") (pintype "passive"))
    )
    (net (code "212") (name "VCC") (class "Default")
      (node (ref "C10") (pin "2") (pinfunction "2_2") (pintype "passive"))
      (node (ref "C17") (pin "1") (pinfunction "1_1") (pintype "passive"))
      (node (ref "C20") (pin "1") (pinfunction "1_1") (pintype "passive"))
      (node (ref "C21") (pin "1") (pinfunction "1_1") (pintype "passive"))
      (node (ref "C22") (pin "1") (pinfunction "1_1") (pintype "passive"))
      (node (ref "C24") (pin "1") (pinfunction "1_1") (pintype "passive"))
      (node (ref "C25") (pin "1") (pinfunction "1_1") (pintype "passive"))
      (node (ref "C26") (pin "1") (pinfunction "1_1") (pintype "passive"))
      (node (ref "C27") (pin "1") (pinfunction "1_1") (pintype "passive"))
      (node (ref "C28") (pin "2") (pinfunction "2_2") (pintype "passive"))
      (node (ref "C35") (pin "1") (pinfunction "1_1") (pintype "passive"))
      (node (ref "C43") (pin "1") (pinfunction "1_1") (pintype "passive"))
      (node (ref "C6") (pin "+") (pinfunction "+_+") (pintype "passive"))
      (node (ref "D1") (pin "C") (pinfunction "C_C") (pintype "passive"))
      (node (ref "D14") (pin "A") (pinfunction "A_A") (pintype "passive"))
      (node (ref "J1") (pin "P$25") (pinfunction "X25_P$25") (pintype "bidirectional"))
      (node (ref "R1") (pin "2") (pinfunction "2_2") (pintype "passive"))
      (node (ref "R14") (pin "1") (pinfunction "1_1") (pintype "passive"))
      (node (ref "R17") (pin "1") (pinfunction "1_1") (pintype "passive"))
      (node (ref "R18") (pin "1") (pinfunction "1_1") (pintype "passive"))
      (node (ref "R19") (pin "1") (pinfunction "1_1") (pintype "passive"))
      (node (ref "R2") (pin "2") (pinfunction "2_2") (pintype "passive"))
      (node (ref "R21") (pin "1") (pinfunction "1_1") (pintype "passive"))
      (node (ref "R25") (pin "2") (pinfunction "2_2") (pintype "passive"))
      (node (ref "R3") (pin "2") (pinfunction "2_2") (pintype "passive"))
      (node (ref "R4") (pin "1") (pinfunction "1_1") (pintype "passive"))
      (node (ref "R5") (pin "2") (pinfunction "2_2") (pintype "passive"))
      (node (ref "R58") (pin "2") (pinfunction "2_2") (pintype "passive"))
      (node (ref "RA1") (pin "1") (pinfunction "1_1") (pintype "passive"))
      (node (ref "U1") (pin "11") (pinfunction "VCC_11") (pintype "power_in"))
      (node (ref "U10") (pin "3") (pinfunction "VO_3") (pintype "passive"))
      (node (ref "U11") (pin "1") (pinfunction "I0_1") (pintype "input"))
      (node (ref "U11") (pin "13") (pinfunction "I2_13") (pintype "input"))
      (node (ref "U14") (pin "3") (pinfunction "CD_3") (pintype "input"))
      (node (ref "U14") (pin "5") (pinfunction "B_5") (pintype "input"))
      (node (ref "U2") (pin "24") (pinfunction "24_24") (pintype "passive"))
      (node (ref "U5") (pin "24") (pinfunction "24_24") (pintype "passive"))
      (node (ref "U7") (pin "12") (pinfunction "P12_12") (pintype "bidirectional"))
      (node (ref "U7") (pin "32") (pinfunction "P32_32") (pintype "bidirectional"))
      (node (ref "U7") (pin "64") (pinfunction "+5V_64") (pintype "power_in"))
      (node (ref "U8") (pin "35") (pinfunction "35_35") (pintype "passive"))
    )
    (net (code "213") (name "VEE") (class "Default")
      (node (ref "R28") (pin "2") (pinfunction "2_2") (pintype "passive"))
      (node (ref "SW1") (pin "P$3C") (pinfunction "P$3C_P$3C") (pintype "bidirectional"))
    )
    (net (code "214") (name "VPP") (class "Default")
      (node (ref "C12") (pin "+") (pinfunction "+_+") (pintype "passive"))
      (node (ref "C15") (pin "1") (pinfunction "1_1") (pintype "passive"))
      (node (ref "C32") (pin "1") (pinfunction "1_1") (pintype "passive"))
      (node (ref "Q3") (pin "3") (pinfunction "E_3") (pintype "passive"))
      (node (ref "Q4") (pin "3") (pinfunction "E_3") (pintype "passive"))
      (node (ref "Q7") (pin "1") (pinfunction "C_1") (pintype "passive"))
      (node (ref "R26") (pin "1") (pinfunction "1_1") (pintype "passive"))
      (node (ref "R27") (pin "2") (pinfunction "2_2") (pintype "passive"))
      (node (ref "R40") (pin "2") (pinfunction "2_2") (pintype "passive"))
      (node (ref "R47") (pin "2") (pinfunction "2_2") (pintype "passive"))
      (node (ref "R54") (pin "1") (pinfunction "1_1") (pintype "passive"))
      (node (ref "R57") (pin "2") (pinfunction "2_2") (pintype "passive"))
      (node (ref "R60") (pin "2") (pinfunction "2_2") (pintype "passive"))
      (node (ref "TR1") (pin "P$1") (pinfunction "A_P$1") (pintype "passive"))
      (node (ref "U12") (pin "10") (pinfunction "10_10") (pintype "passive"))
    )
    (net (code "215") (name "unconnected-(J5-Pad4)") (class "Default")
      (node (ref "J5") (pin "4") (pinfunction "4_4") (pintype "bidirectional"))
    )
    (net (code "216") (name "unconnected-(J5-Pad5)") (class "Default")
      (node (ref "J5") (pin "5") (pinfunction "5_5") (pintype "bidirectional"))
    )
    (net (code "217") (name "unconnected-(SW2-S-Pad1)") (class "Default")
      (node (ref "SW2") (pin "1") (pinfunction "S_1") (pintype "passive"))
    )
    (net (code "218") (name "unconnected-(U5-Pad21)") (class "Default")
      (node (ref "U5") (pin "21") (pinfunction "21_21") (pintype "passive"))
    )
    (net (code "219") (name "unconnected-(U6A-INH-Pad15)") (class "Default")
      (node (ref "U6") (pin "15") (pinfunction "INH_15") (pintype "input"))
    )
    (net (code "220") (name "unconnected-(U6A-~{QH}-Pad7)") (class "Default")
      (node (ref "U6") (pin "7") (pinfunction "~{QH}_7") (pintype "output"))
    )
    (net (code "221") (name "unconnected-(U8-Pad7)") (class "Default")
      (node (ref "U8") (pin "7") (pinfunction "7_7") (pintype "passive"))
    )
    (net (code "222") (name "unconnected-(U8-Pad8)") (class "Default")
      (node (ref "U8") (pin "8") (pinfunction "8_8") (pintype "passive"))
    )
    (net (code "223") (name "Φ") (class "Default")
      (node (ref "J1") (pin "P$8") (pinfunction "X8_P$8") (pintype "bidirectional"))
      (node (ref "U1") (pin "6") (pinfunction "CLK_6") (pintype "input"))
      (node (ref "U7") (pin "31") (pinfunction "Φ_31") (pintype "bidirectional"))
    )
  )
)
